# USB_Hub_Switch.net
KiCad netlist of a schematic drawn in EasyEDA Pro
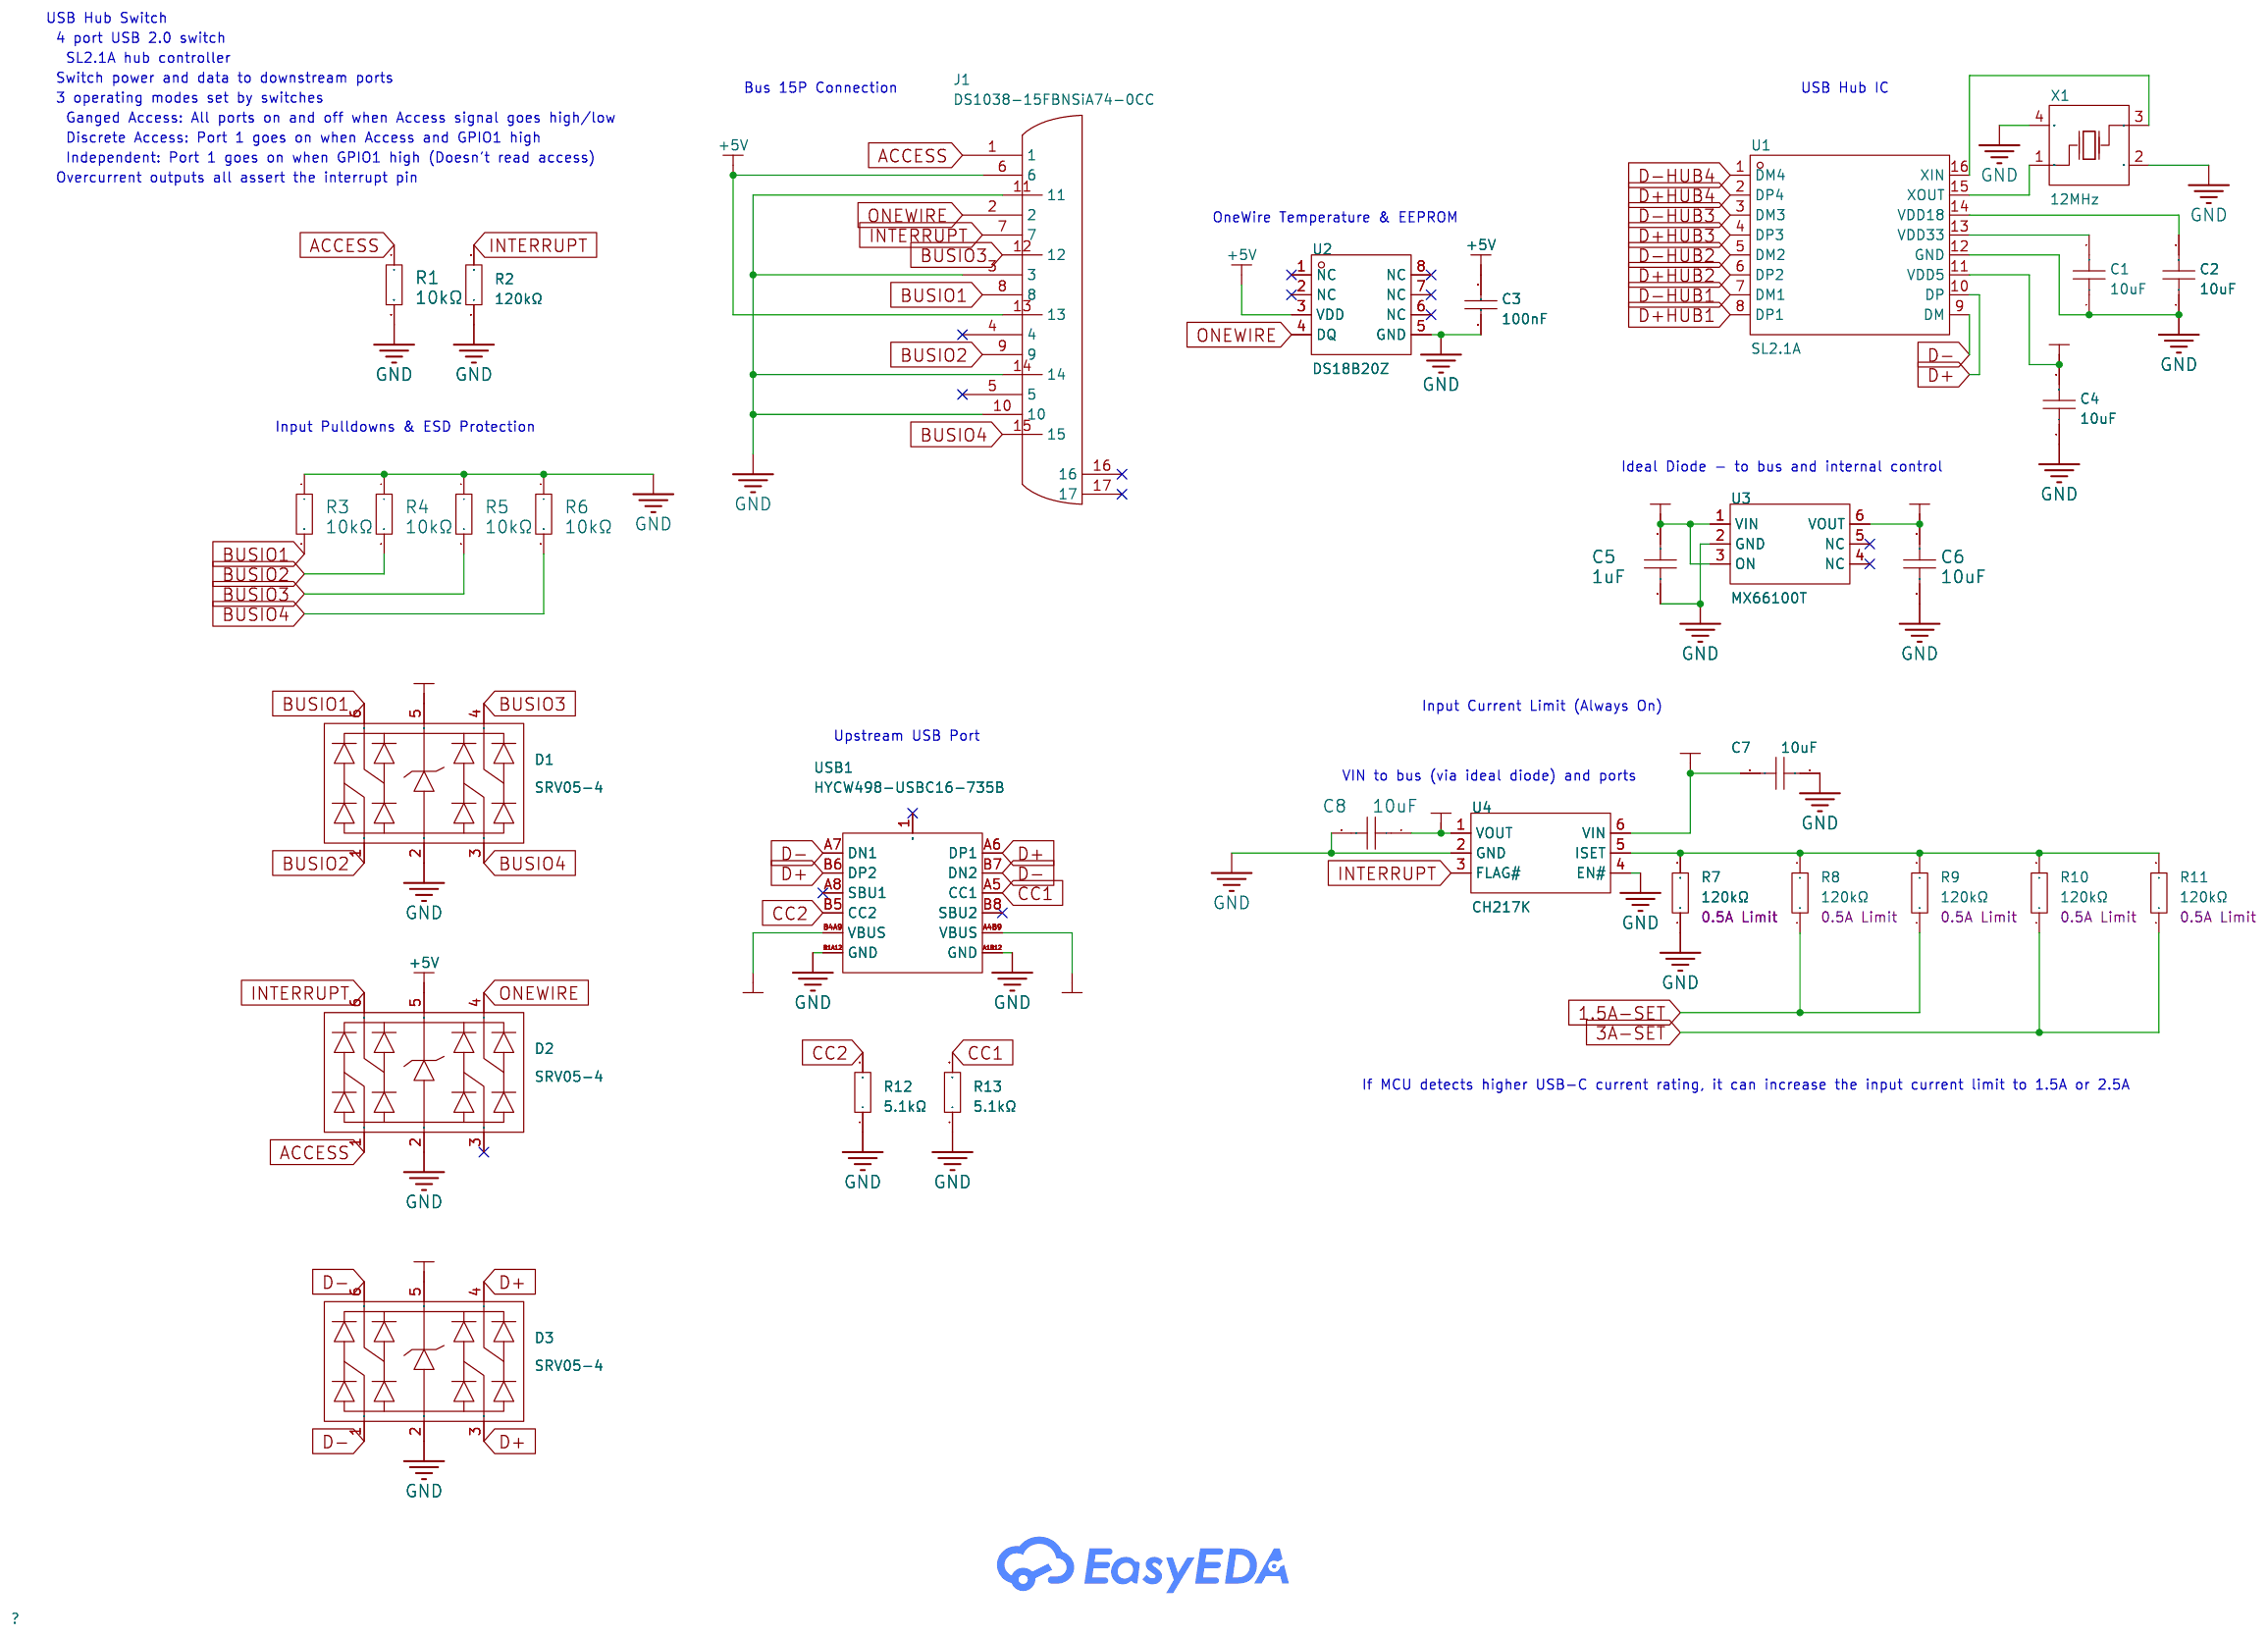
[diagram p0: Upstream Ports]
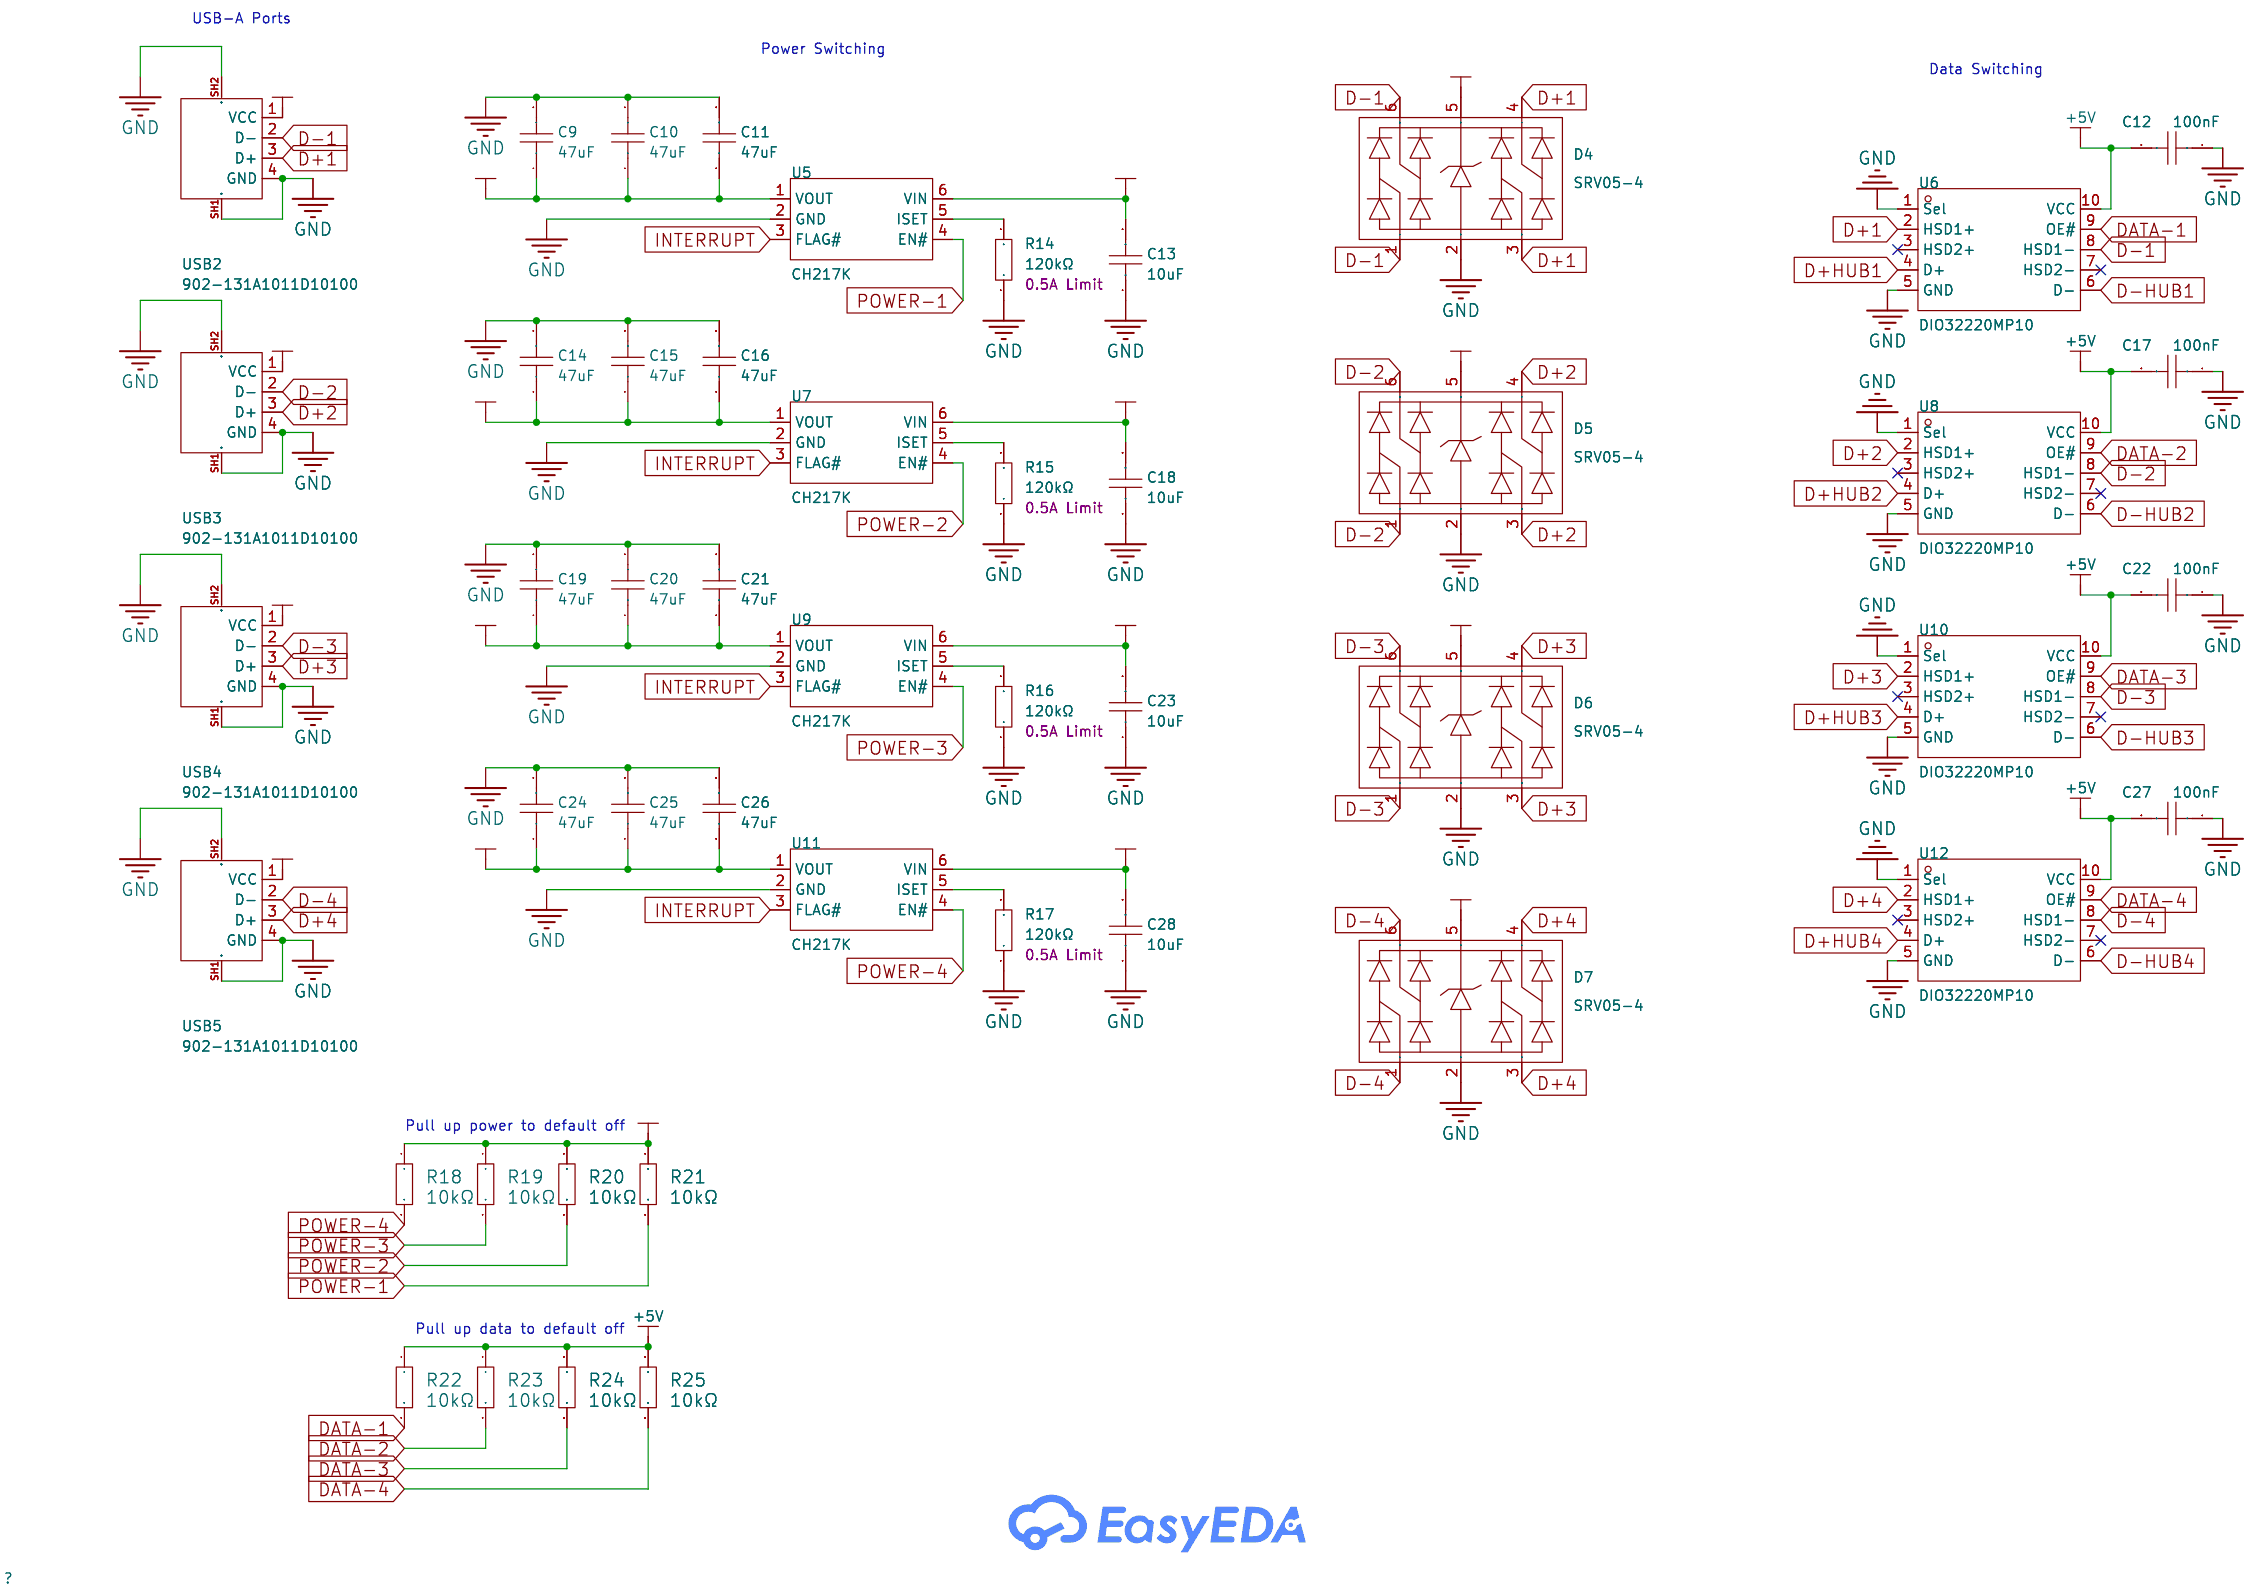
[diagram p1: Downstream Ports]
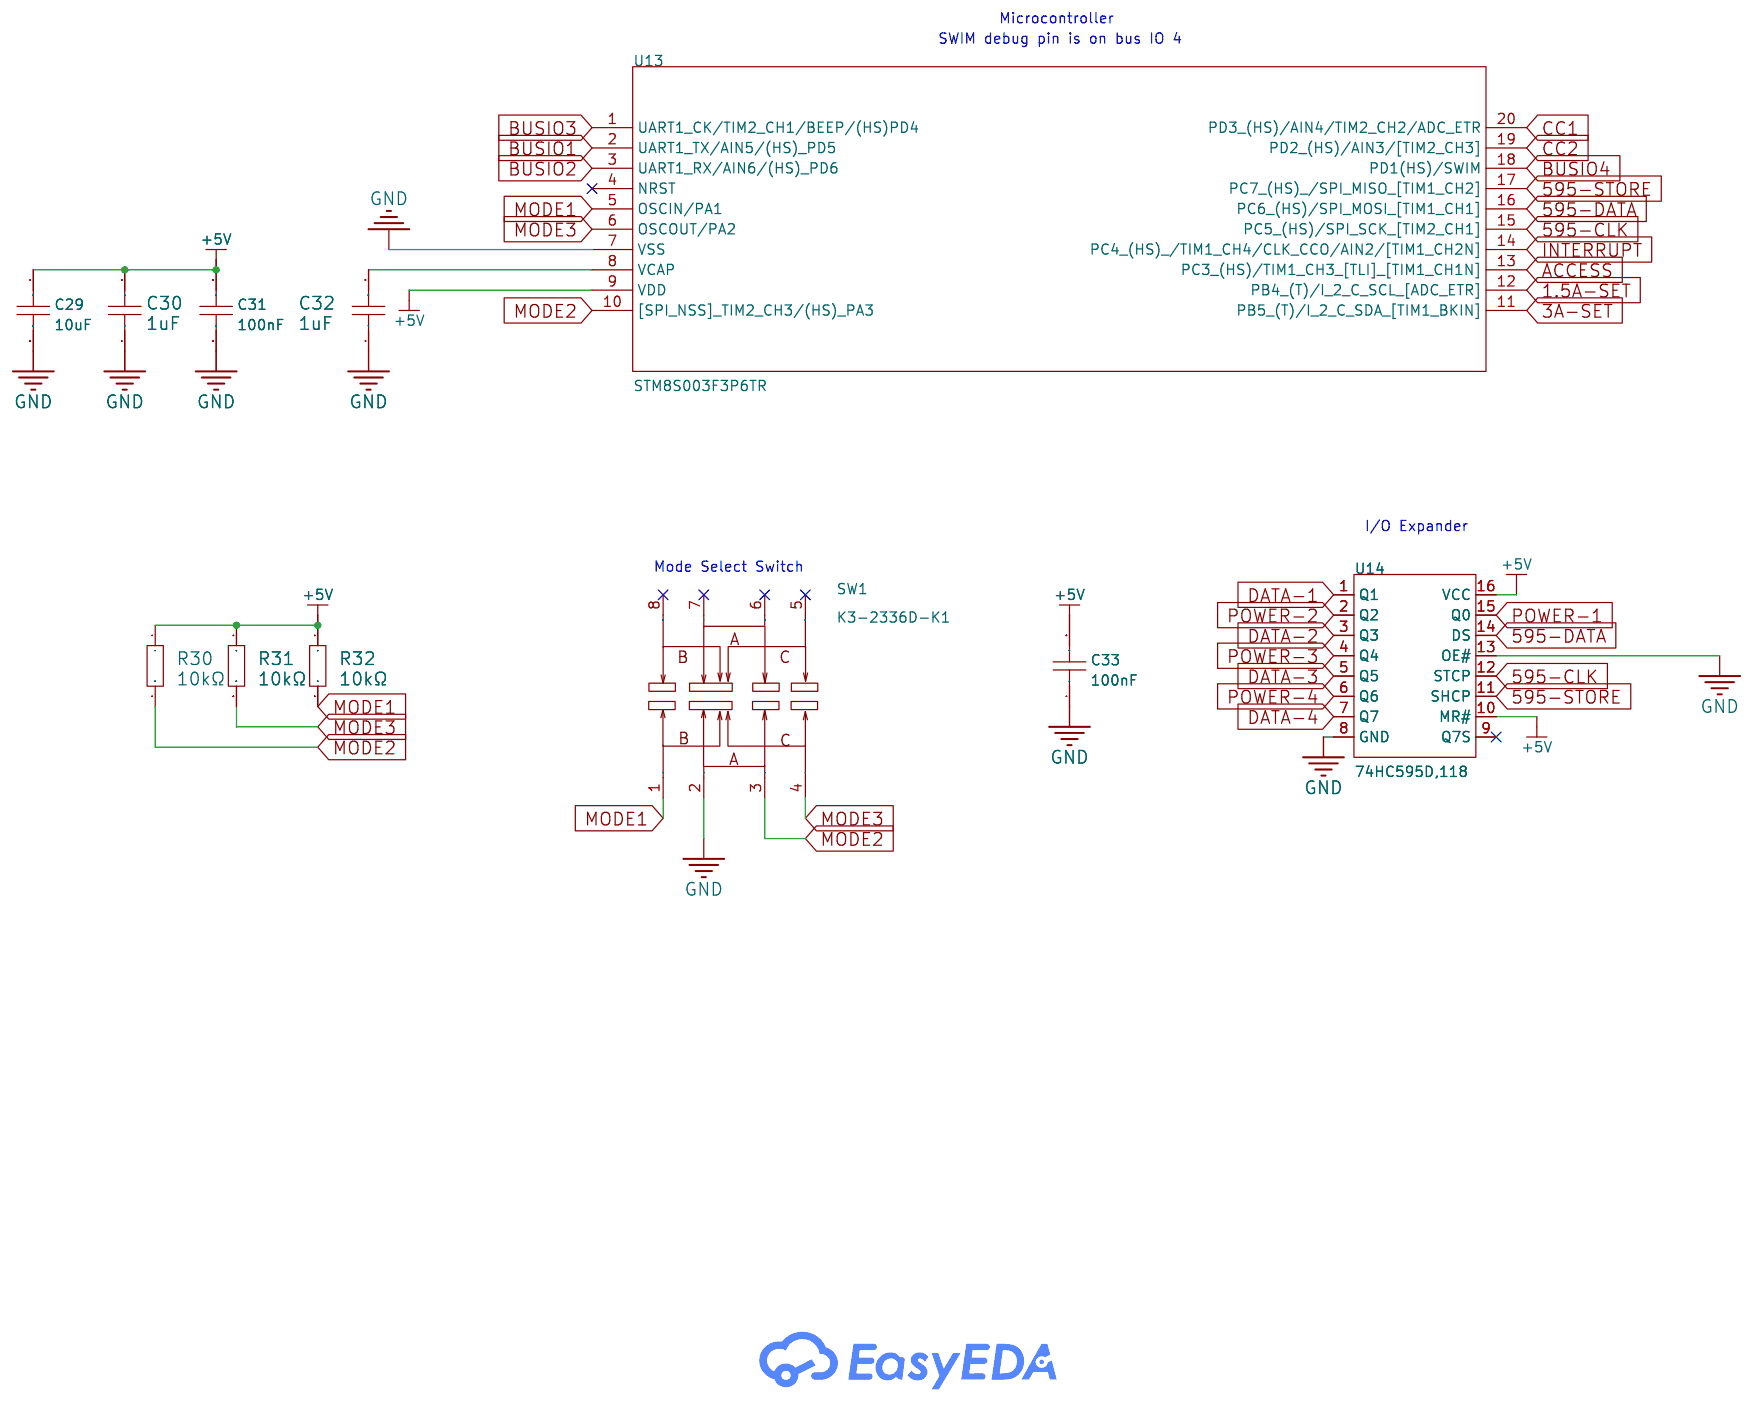
[diagram p2: Microcontroller]
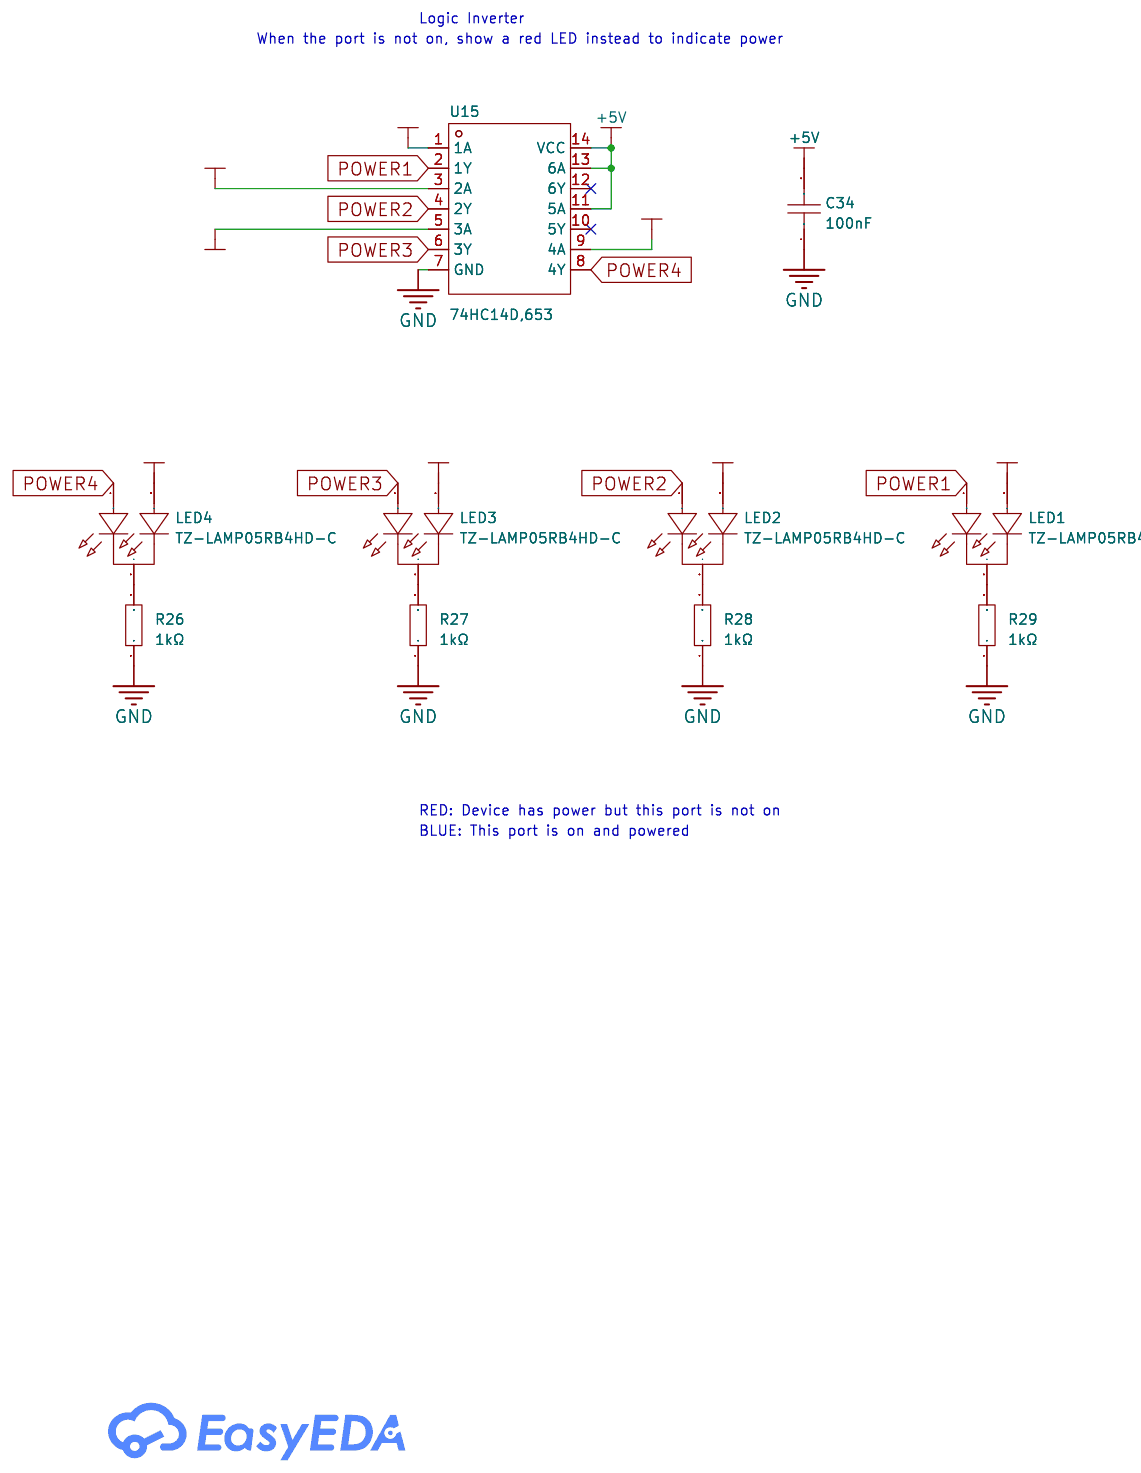
[diagram p3: Status LEDs]

(export (version "E")
  (design (tool "Eeschema 10.0.6"))
  (components
    (comp (ref "C1")
      (value "10uF")
      (footprint "easyedapro:C0603")
      (fields
        (field (name "Manufacturer Part") "CL10A106MA8NRNC")
        (field (name "Manufacturer") "SAMSUNG(三星)")
      )
      (libsource (lib "easyedapro") (part "CL10A106MA8NRNC"))
    )
    (comp (ref "C2")
      (value "10uF")
      (footprint "easyedapro:C0603")
      (fields
        (field (name "Manufacturer Part") "CL10A106MA8NRNC")
        (field (name "Manufacturer") "SAMSUNG(三星)")
      )
      (libsource (lib "easyedapro") (part "CL10A106MA8NRNC"))
    )
    (comp (ref "C3")
      (value "100nF")
      (footprint "easyedapro:C0805")
      (description "Capacitance:100nF Tolerance:±10% Tolerance:±10% Voltage Rating:100V Temperature Coefficient:X7R")
      (fields
        (field (name "Manufacturer Part") "CL21B104KCFNNNE")
        (field (name "Manufacturer") "SAMSUNG(三星)")
      )
      (libsource (lib "easyedapro") (part "CL21B104KCFNNNE"))
    )
    (comp (ref "C4")
      (value "10uF")
      (footprint "easyedapro:C0603")
      (fields
        (field (name "Manufacturer Part") "CL10A106MA8NRNC")
        (field (name "Manufacturer") "SAMSUNG(三星)")
      )
      (libsource (lib "easyedapro") (part "CL10A106MA8NRNC"))
    )
    (comp (ref "C5")
      (value "1uF")
      (footprint "easyedapro:C0603")
      (fields
        (field (name "Manufacturer Part") "CL10A105KB8NNNC")
        (field (name "Manufacturer") "SAMSUNG(三星)")
      )
      (libsource (lib "easyedapro") (part "CL10A105KB8NNNC"))
    )
    (comp (ref "C6")
      (value "10uF")
      (footprint "easyedapro:C0603")
      (description "Capacitance:10uF Tolerance:±20% Tolerance:±20% Voltage Rating:25V Temperature Coefficient:X5R")
      (fields
        (field (name "Manufacturer Part") "CL10A106MA8NRNC")
        (field (name "Manufacturer") "SAMSUNG(三星)")
      )
      (libsource (lib "easyedapro") (part "CL10A106MA8NRNC"))
    )
    (comp (ref "C7")
      (value "10uF")
      (footprint "easyedapro:C0603")
      (fields
        (field (name "Manufacturer Part") "CL10A106MA8NRNC")
        (field (name "Manufacturer") "SAMSUNG(三星)")
      )
      (libsource (lib "easyedapro") (part "CL10A106MA8NRNC"))
    )
    (comp (ref "C8")
      (value "10uF")
      (footprint "easyedapro:C0603")
      (description "Capacitance:10uF Tolerance:±20% Tolerance:±20% Voltage Rating:25V Temperature Coefficient:X5R")
      (fields
        (field (name "Manufacturer Part") "CL10A106MA8NRNC")
        (field (name "Manufacturer") "SAMSUNG(三星)")
      )
      (libsource (lib "easyedapro") (part "CL10A106MA8NRNC"))
    )
    (comp (ref "D1")
      (value "SRV05-4")
      (footprint "easyedapro:SOT-23-6_L2.9-W1.6-P0.95-LS2.8-BL")
      (fields (field (name "Manufacturer") "TECH PUBLIC(台舟)"))
      (libsource (lib "easyedapro") (part "SRV05-4_C558418"))
    )
    (comp (ref "D2")
      (value "SRV05-4")
      (footprint "easyedapro:SOT-23-6_L2.9-W1.6-P0.95-LS2.8-BL")
      (fields (field (name "Manufacturer") "TECH PUBLIC(台舟)"))
      (libsource (lib "easyedapro") (part "SRV05-4_C558418"))
    )
    (comp (ref "D3")
      (value "SRV05-4")
      (footprint "easyedapro:SOT-23-6_L2.9-W1.6-P0.95-LS2.8-BL")
      (fields (field (name "Manufacturer") "TECH PUBLIC(台舟)"))
      (libsource (lib "easyedapro") (part "SRV05-4_C558418"))
    )
    (comp (ref "J1")
      (value "DS1038-15FBNSiA74-0CC")
      (footprint "easyedapro:DSUB-TH_DS1038-15FBNSIA74-0CC")
      (fields (field (name "Manufacturer") "CONNFLY"))
      (libsource (lib "easyedapro") (part "DS1038-15FBNSIA74-0CC"))
    )
    (comp (ref "R1")
      (value "10kΩ")
      (footprint "easyedapro:R0603")
      (fields
        (field (name "Manufacturer Part") "0603WAF1002T5E")
        (field (name "Manufacturer") "UNI-ROYAL(厚声)")
      )
      (libsource (lib "easyedapro") (part "0603WAF1002T5E"))
    )
    (comp (ref "R2")
      (value "120kΩ")
      (footprint "easyedapro:R0603")
      (fields
        (field (name "Manufacturer Part") "0603WAF1203T5E")
        (field (name "Manufacturer") "UNI-ROYAL(厚声)")
      )
      (libsource (lib "easyedapro") (part "0603WAF1203T5E"))
    )
    (comp (ref "R3")
      (value "10kΩ")
      (footprint "easyedapro:R0603")
      (fields
        (field (name "Manufacturer Part") "0603WAF1002T5E")
        (field (name "Manufacturer") "UNI-ROYAL(厚声)")
      )
      (libsource (lib "easyedapro") (part "0603WAF1002T5E"))
    )
    (comp (ref "R4")
      (value "10kΩ")
      (footprint "easyedapro:R0603")
      (fields
        (field (name "Manufacturer Part") "0603WAF1002T5E")
        (field (name "Manufacturer") "UNI-ROYAL(厚声)")
      )
      (libsource (lib "easyedapro") (part "0603WAF1002T5E"))
    )
    (comp (ref "R5")
      (value "10kΩ")
      (footprint "easyedapro:R0603")
      (fields
        (field (name "Manufacturer Part") "0603WAF1002T5E")
        (field (name "Manufacturer") "UNI-ROYAL(厚声)")
      )
      (libsource (lib "easyedapro") (part "0603WAF1002T5E"))
    )
    (comp (ref "R6")
      (value "10kΩ")
      (footprint "easyedapro:R0603")
      (fields
        (field (name "Manufacturer Part") "0603WAF1002T5E")
        (field (name "Manufacturer") "UNI-ROYAL(厚声)")
      )
      (libsource (lib "easyedapro") (part "0603WAF1002T5E"))
    )
    (comp (ref "R7")
      (value "120kΩ")
      (footprint "easyedapro:R0603")
      (fields
        (field (name "Manufacturer Part") "0603WAF1203T5E")
        (field (name "Manufacturer") "UNI-ROYAL(厚声)")
        (field (name "Note") "0.5A Limit")
      )
      (libsource (lib "easyedapro") (part "0603WAF1203T5E"))
    )
    (comp (ref "R8")
      (value "120kΩ")
      (footprint "easyedapro:R0603")
      (fields
        (field (name "Manufacturer Part") "0603WAF1203T5E")
        (field (name "Manufacturer") "UNI-ROYAL(厚声)")
        (field (name "Note") "0.5A Limit")
      )
      (libsource (lib "easyedapro") (part "0603WAF1203T5E"))
    )
    (comp (ref "R9")
      (value "120kΩ")
      (footprint "easyedapro:R0603")
      (fields
        (field (name "Manufacturer Part") "0603WAF1203T5E")
        (field (name "Manufacturer") "UNI-ROYAL(厚声)")
        (field (name "Note") "0.5A Limit")
      )
      (libsource (lib "easyedapro") (part "0603WAF1203T5E"))
    )
    (comp (ref "R10")
      (value "120kΩ")
      (footprint "easyedapro:R0603")
      (fields
        (field (name "Manufacturer Part") "0603WAF1203T5E")
        (field (name "Manufacturer") "UNI-ROYAL(厚声)")
        (field (name "Note") "0.5A Limit")
      )
      (libsource (lib "easyedapro") (part "0603WAF1203T5E"))
    )
    (comp (ref "R11")
      (value "120kΩ")
      (footprint "easyedapro:R0603")
      (fields
        (field (name "Manufacturer Part") "0603WAF1203T5E")
        (field (name "Manufacturer") "UNI-ROYAL(厚声)")
        (field (name "Note") "0.5A Limit")
      )
      (libsource (lib "easyedapro") (part "0603WAF1203T5E"))
    )
    (comp (ref "R12")
      (value "5.1kΩ")
      (footprint "easyedapro:R0603")
      (fields
        (field (name "Manufacturer Part") "0603WAF5101T5E")
        (field (name "Manufacturer") "UNI-ROYAL(厚声)")
      )
      (libsource (lib "easyedapro") (part "0603WAF5101T5E"))
    )
    (comp (ref "R13")
      (value "5.1kΩ")
      (footprint "easyedapro:R0603")
      (fields
        (field (name "Manufacturer Part") "0603WAF5101T5E")
        (field (name "Manufacturer") "UNI-ROYAL(厚声)")
      )
      (libsource (lib "easyedapro") (part "0603WAF5101T5E"))
    )
    (comp (ref "U1")
      (value "SL2.1A")
      (footprint "easyedapro:SOP-16_L10.0-W3.9-P1.27-LS6.0-BL")
      (fields (field (name "Manufacturer") "CoreChips(和芯润德)"))
      (libsource (lib "easyedapro") (part "SL2.1A"))
    )
    (comp (ref "U2")
      (value "DS18B20Z")
      (footprint "easyedapro:SOP-8_L4.9-W3.9-P1.27-LS6.0-BL")
      (description "Resolution:±0.4°C Resolution:±0.4°C Supply Voltage:2.5V~5.5V Supply Voltage:2.5V~5.5V")
      (fields (field (name "Manufacturer") "UMW(友台半导体)"))
      (libsource (lib "easyedapro") (part "DS18B20Z"))
    )
    (comp (ref "U3")
      (value "MX66100T")
      (footprint "easyedapro:SOT-23-6_L2.9-W1.6-P0.95-LS2.9-BL")
      (fields (field (name "Manufacturer") "Wuxi Maxinmicro(无锡明芯微)"))
      (libsource (lib "easyedapro") (part "MX66100T"))
    )
    (comp (ref "U4")
      (value "CH217K")
      (footprint "easyedapro:SOT-23-6_L2.9-W1.6-P0.95-LS2.8-BL")
      (fields (field (name "Manufacturer") "WCH(南京沁恒)"))
      (libsource (lib "easyedapro") (part "CH217K"))
    )
    (comp (ref "USB1")
      (value "HYCW498-USBC16-735B")
      (footprint "easyedapro:USB-C-SMD_HYCW498-USBC16-735B")
      (fields (field (name "Manufacturer") "华宇创"))
      (libsource (lib "easyedapro") (part "HYCW498-USBC16-735B"))
    )
    (comp (ref "X1")
      (value "12MHz")
      (footprint "easyedapro:OSC-SMD_4P-L3.2-W2.5-BL")
      (fields (field (name "Manufacturer Part") "X322512MSB4SI") (field (name "Manufacturer") "YXC(扬兴晶振)"))
      (libsource (lib "easyedapro") (part "X322512MSB4SI"))
    )
    (comp (ref "C9")
      (value "47uF")
      (footprint "easyedapro:C1206")
      (description "Capacitance:47uF Tolerance:±20% Tolerance:±20% Voltage Rating:10V Temperature Coefficient:X5R")
      (fields
        (field (name "Manufacturer Part") "CL31A476MPHNNNE")
        (field (name "Manufacturer") "SAMSUNG(三星)")
      )
      (libsource (lib "easyedapro") (part "CL31A476MPHNNNE"))
    )
    (comp (ref "C10")
      (value "47uF")
      (footprint "easyedapro:C1206")
      (description "Capacitance:47uF Tolerance:±20% Tolerance:±20% Voltage Rating:10V Temperature Coefficient:X5R")
      (fields
        (field (name "Manufacturer Part") "CL31A476MPHNNNE")
        (field (name "Manufacturer") "SAMSUNG(三星)")
      )
      (libsource (lib "easyedapro") (part "CL31A476MPHNNNE"))
    )
    (comp (ref "C11")
      (value "47uF")
      (footprint "easyedapro:C1206")
      (description "Capacitance:47uF Tolerance:±20% Tolerance:±20% Voltage Rating:10V Temperature Coefficient:X5R")
      (fields
        (field (name "Manufacturer Part") "CL31A476MPHNNNE")
        (field (name "Manufacturer") "SAMSUNG(三星)")
      )
      (libsource (lib "easyedapro") (part "CL31A476MPHNNNE"))
    )
    (comp (ref "C12")
      (value "100nF")
      (footprint "easyedapro:C0603")
      (description "Capacitance:100nF Tolerance:±10% Tolerance:±10% Voltage Rating:50V Temperature Coefficient:X7R")
      (fields
        (field (name "Manufacturer Part") "CC0603KRX7R9BB104")
        (field (name "Manufacturer") "YAGEO(国巨)")
      )
      (libsource (lib "easyedapro") (part "CC0603KRX7R9BB104"))
    )
    (comp (ref "C13")
      (value "10uF")
      (footprint "easyedapro:C0603")
      (fields
        (field (name "Manufacturer Part") "CL10A106MA8NRNC")
        (field (name "Manufacturer") "SAMSUNG(三星)")
      )
      (libsource (lib "easyedapro") (part "CL10A106MA8NRNC"))
    )
    (comp (ref "C14")
      (value "47uF")
      (footprint "easyedapro:C1206")
      (description "Capacitance:47uF Tolerance:±20% Tolerance:±20% Voltage Rating:10V Temperature Coefficient:X5R")
      (fields
        (field (name "Manufacturer Part") "CL31A476MPHNNNE")
        (field (name "Manufacturer") "SAMSUNG(三星)")
      )
      (libsource (lib "easyedapro") (part "CL31A476MPHNNNE"))
    )
    (comp (ref "C15")
      (value "47uF")
      (footprint "easyedapro:C1206")
      (description "Capacitance:47uF Tolerance:±20% Tolerance:±20% Voltage Rating:10V Temperature Coefficient:X5R")
      (fields
        (field (name "Manufacturer Part") "CL31A476MPHNNNE")
        (field (name "Manufacturer") "SAMSUNG(三星)")
      )
      (libsource (lib "easyedapro") (part "CL31A476MPHNNNE"))
    )
    (comp (ref "C16")
      (value "47uF")
      (footprint "easyedapro:C1206")
      (description "Capacitance:47uF Tolerance:±20% Tolerance:±20% Voltage Rating:10V Temperature Coefficient:X5R")
      (fields
        (field (name "Manufacturer Part") "CL31A476MPHNNNE")
        (field (name "Manufacturer") "SAMSUNG(三星)")
      )
      (libsource (lib "easyedapro") (part "CL31A476MPHNNNE"))
    )
    (comp (ref "C17")
      (value "100nF")
      (footprint "easyedapro:C0603")
      (description "Capacitance:100nF Tolerance:±10% Tolerance:±10% Voltage Rating:50V Temperature Coefficient:X7R")
      (fields
        (field (name "Manufacturer Part") "CC0603KRX7R9BB104")
        (field (name "Manufacturer") "YAGEO(国巨)")
      )
      (libsource (lib "easyedapro") (part "CC0603KRX7R9BB104"))
    )
    (comp (ref "C18")
      (value "10uF")
      (footprint "easyedapro:C0603")
      (fields
        (field (name "Manufacturer Part") "CL10A106MA8NRNC")
        (field (name "Manufacturer") "SAMSUNG(三星)")
      )
      (libsource (lib "easyedapro") (part "CL10A106MA8NRNC"))
    )
    (comp (ref "C19")
      (value "47uF")
      (footprint "easyedapro:C1206")
      (description "Capacitance:47uF Tolerance:±20% Tolerance:±20% Voltage Rating:10V Temperature Coefficient:X5R")
      (fields
        (field (name "Manufacturer Part") "CL31A476MPHNNNE")
        (field (name "Manufacturer") "SAMSUNG(三星)")
      )
      (libsource (lib "easyedapro") (part "CL31A476MPHNNNE"))
    )
    (comp (ref "C20")
      (value "47uF")
      (footprint "easyedapro:C1206")
      (description "Capacitance:47uF Tolerance:±20% Tolerance:±20% Voltage Rating:10V Temperature Coefficient:X5R")
      (fields
        (field (name "Manufacturer Part") "CL31A476MPHNNNE")
        (field (name "Manufacturer") "SAMSUNG(三星)")
      )
      (libsource (lib "easyedapro") (part "CL31A476MPHNNNE"))
    )
    (comp (ref "C21")
      (value "47uF")
      (footprint "easyedapro:C1206")
      (description "Capacitance:47uF Tolerance:±20% Tolerance:±20% Voltage Rating:10V Temperature Coefficient:X5R")
      (fields
        (field (name "Manufacturer Part") "CL31A476MPHNNNE")
        (field (name "Manufacturer") "SAMSUNG(三星)")
      )
      (libsource (lib "easyedapro") (part "CL31A476MPHNNNE"))
    )
    (comp (ref "C22")
      (value "100nF")
      (footprint "easyedapro:C0603")
      (description "Capacitance:100nF Tolerance:±10% Tolerance:±10% Voltage Rating:50V Temperature Coefficient:X7R")
      (fields
        (field (name "Manufacturer Part") "CC0603KRX7R9BB104")
        (field (name "Manufacturer") "YAGEO(国巨)")
      )
      (libsource (lib "easyedapro") (part "CC0603KRX7R9BB104"))
    )
    (comp (ref "C23")
      (value "10uF")
      (footprint "easyedapro:C0603")
      (fields
        (field (name "Manufacturer Part") "CL10A106MA8NRNC")
        (field (name "Manufacturer") "SAMSUNG(三星)")
      )
      (libsource (lib "easyedapro") (part "CL10A106MA8NRNC"))
    )
    (comp (ref "C24")
      (value "47uF")
      (footprint "easyedapro:C1206")
      (description "Capacitance:47uF Tolerance:±20% Tolerance:±20% Voltage Rating:10V Temperature Coefficient:X5R")
      (fields
        (field (name "Manufacturer Part") "CL31A476MPHNNNE")
        (field (name "Manufacturer") "SAMSUNG(三星)")
      )
      (libsource (lib "easyedapro") (part "CL31A476MPHNNNE"))
    )
    (comp (ref "C25")
      (value "47uF")
      (footprint "easyedapro:C1206")
      (description "Capacitance:47uF Tolerance:±20% Tolerance:±20% Voltage Rating:10V Temperature Coefficient:X5R")
      (fields
        (field (name "Manufacturer Part") "CL31A476MPHNNNE")
        (field (name "Manufacturer") "SAMSUNG(三星)")
      )
      (libsource (lib "easyedapro") (part "CL31A476MPHNNNE"))
    )
    (comp (ref "C26")
      (value "47uF")
      (footprint "easyedapro:C1206")
      (description "Capacitance:47uF Tolerance:±20% Tolerance:±20% Voltage Rating:10V Temperature Coefficient:X5R")
      (fields
        (field (name "Manufacturer Part") "CL31A476MPHNNNE")
        (field (name "Manufacturer") "SAMSUNG(三星)")
      )
      (libsource (lib "easyedapro") (part "CL31A476MPHNNNE"))
    )
    (comp (ref "C27")
      (value "100nF")
      (footprint "easyedapro:C0603")
      (description "Capacitance:100nF Tolerance:±10% Tolerance:±10% Voltage Rating:50V Temperature Coefficient:X7R")
      (fields
        (field (name "Manufacturer Part") "CC0603KRX7R9BB104")
        (field (name "Manufacturer") "YAGEO(国巨)")
      )
      (libsource (lib "easyedapro") (part "CC0603KRX7R9BB104"))
    )
    (comp (ref "C28")
      (value "10uF")
      (footprint "easyedapro:C0603")
      (fields
        (field (name "Manufacturer Part") "CL10A106MA8NRNC")
        (field (name "Manufacturer") "SAMSUNG(三星)")
      )
      (libsource (lib "easyedapro") (part "CL10A106MA8NRNC"))
    )
    (comp (ref "D4")
      (value "SRV05-4")
      (footprint "easyedapro:SOT-23-6_L2.9-W1.6-P0.95-LS2.8-BL")
      (fields (field (name "Manufacturer") "TECH PUBLIC(台舟)"))
      (libsource (lib "easyedapro") (part "SRV05-4_C558418"))
    )
    (comp (ref "D5")
      (value "SRV05-4")
      (footprint "easyedapro:SOT-23-6_L2.9-W1.6-P0.95-LS2.8-BL")
      (fields (field (name "Manufacturer") "TECH PUBLIC(台舟)"))
      (libsource (lib "easyedapro") (part "SRV05-4_C558418"))
    )
    (comp (ref "D6")
      (value "SRV05-4")
      (footprint "easyedapro:SOT-23-6_L2.9-W1.6-P0.95-LS2.8-BL")
      (fields (field (name "Manufacturer") "TECH PUBLIC(台舟)"))
      (libsource (lib "easyedapro") (part "SRV05-4_C558418"))
    )
    (comp (ref "D7")
      (value "SRV05-4")
      (footprint "easyedapro:SOT-23-6_L2.9-W1.6-P0.95-LS2.8-BL")
      (fields (field (name "Manufacturer") "TECH PUBLIC(台舟)"))
      (libsource (lib "easyedapro") (part "SRV05-4_C558418"))
    )
    (comp (ref "R14")
      (value "120kΩ")
      (footprint "easyedapro:R0603")
      (fields
        (field (name "Manufacturer Part") "0603WAF1203T5E")
        (field (name "Manufacturer") "UNI-ROYAL(厚声)")
        (field (name "Note") "0.5A Limit")
      )
      (libsource (lib "easyedapro") (part "0603WAF1203T5E"))
    )
    (comp (ref "R15")
      (value "120kΩ")
      (footprint "easyedapro:R0603")
      (fields
        (field (name "Manufacturer Part") "0603WAF1203T5E")
        (field (name "Manufacturer") "UNI-ROYAL(厚声)")
        (field (name "Note") "0.5A Limit")
      )
      (libsource (lib "easyedapro") (part "0603WAF1203T5E"))
    )
    (comp (ref "R16")
      (value "120kΩ")
      (footprint "easyedapro:R0603")
      (fields
        (field (name "Manufacturer Part") "0603WAF1203T5E")
        (field (name "Manufacturer") "UNI-ROYAL(厚声)")
        (field (name "Note") "0.5A Limit")
      )
      (libsource (lib "easyedapro") (part "0603WAF1203T5E"))
    )
    (comp (ref "R17")
      (value "120kΩ")
      (footprint "easyedapro:R0603")
      (fields
        (field (name "Manufacturer Part") "0603WAF1203T5E")
        (field (name "Manufacturer") "UNI-ROYAL(厚声)")
        (field (name "Note") "0.5A Limit")
      )
      (libsource (lib "easyedapro") (part "0603WAF1203T5E"))
    )
    (comp (ref "R18")
      (value "10kΩ")
      (footprint "easyedapro:R0603")
      (fields
        (field (name "Manufacturer Part") "0603WAF1002T5E")
        (field (name "Manufacturer") "UNI-ROYAL(厚声)")
      )
      (libsource (lib "easyedapro") (part "0603WAF1002T5E"))
    )
    (comp (ref "R19")
      (value "10kΩ")
      (footprint "easyedapro:R0603")
      (fields
        (field (name "Manufacturer Part") "0603WAF1002T5E")
        (field (name "Manufacturer") "UNI-ROYAL(厚声)")
      )
      (libsource (lib "easyedapro") (part "0603WAF1002T5E"))
    )
    (comp (ref "R20")
      (value "10kΩ")
      (footprint "easyedapro:R0603")
      (fields
        (field (name "Manufacturer Part") "0603WAF1002T5E")
        (field (name "Manufacturer") "UNI-ROYAL(厚声)")
      )
      (libsource (lib "easyedapro") (part "0603WAF1002T5E"))
    )
    (comp (ref "R21")
      (value "10kΩ")
      (footprint "easyedapro:R0603")
      (fields
        (field (name "Manufacturer Part") "0603WAF1002T5E")
        (field (name "Manufacturer") "UNI-ROYAL(厚声)")
      )
      (libsource (lib "easyedapro") (part "0603WAF1002T5E"))
    )
    (comp (ref "R22")
      (value "10kΩ")
      (footprint "easyedapro:R0603")
      (fields
        (field (name "Manufacturer Part") "0603WAF1002T5E")
        (field (name "Manufacturer") "UNI-ROYAL(厚声)")
      )
      (libsource (lib "easyedapro") (part "0603WAF1002T5E"))
    )
    (comp (ref "R23")
      (value "10kΩ")
      (footprint "easyedapro:R0603")
      (fields
        (field (name "Manufacturer Part") "0603WAF1002T5E")
        (field (name "Manufacturer") "UNI-ROYAL(厚声)")
      )
      (libsource (lib "easyedapro") (part "0603WAF1002T5E"))
    )
    (comp (ref "R24")
      (value "10kΩ")
      (footprint "easyedapro:R0603")
      (fields
        (field (name "Manufacturer Part") "0603WAF1002T5E")
        (field (name "Manufacturer") "UNI-ROYAL(厚声)")
      )
      (libsource (lib "easyedapro") (part "0603WAF1002T5E"))
    )
    (comp (ref "R25")
      (value "10kΩ")
      (footprint "easyedapro:R0603")
      (fields
        (field (name "Manufacturer Part") "0603WAF1002T5E")
        (field (name "Manufacturer") "UNI-ROYAL(厚声)")
      )
      (libsource (lib "easyedapro") (part "0603WAF1002T5E"))
    )
    (comp (ref "U5")
      (value "CH217K")
      (footprint "easyedapro:SOT-23-6_L2.9-W1.6-P0.95-LS2.8-BL")
      (fields (field (name "Manufacturer") "WCH(南京沁恒)"))
      (libsource (lib "easyedapro") (part "CH217K"))
    )
    (comp (ref "U6")
      (value "DIO32220MP10")
      (footprint "easyedapro:MSOP-10_L3.0-W3.0-P0.50-LS5.0-BL")
      (fields (field (name "Manufacturer") "DIOO(帝奥微)"))
      (libsource (lib "easyedapro") (part "DIO32220MP10"))
    )
    (comp (ref "U7")
      (value "CH217K")
      (footprint "easyedapro:SOT-23-6_L2.9-W1.6-P0.95-LS2.8-BL")
      (fields (field (name "Manufacturer") "WCH(南京沁恒)"))
      (libsource (lib "easyedapro") (part "CH217K"))
    )
    (comp (ref "U8")
      (value "DIO32220MP10")
      (footprint "easyedapro:MSOP-10_L3.0-W3.0-P0.50-LS5.0-BL")
      (fields (field (name "Manufacturer") "DIOO(帝奥微)"))
      (libsource (lib "easyedapro") (part "DIO32220MP10"))
    )
    (comp (ref "U9")
      (value "CH217K")
      (footprint "easyedapro:SOT-23-6_L2.9-W1.6-P0.95-LS2.8-BL")
      (fields (field (name "Manufacturer") "WCH(南京沁恒)"))
      (libsource (lib "easyedapro") (part "CH217K"))
    )
    (comp (ref "U10")
      (value "DIO32220MP10")
      (footprint "easyedapro:MSOP-10_L3.0-W3.0-P0.50-LS5.0-BL")
      (fields (field (name "Manufacturer") "DIOO(帝奥微)"))
      (libsource (lib "easyedapro") (part "DIO32220MP10"))
    )
    (comp (ref "U11")
      (value "CH217K")
      (footprint "easyedapro:SOT-23-6_L2.9-W1.6-P0.95-LS2.8-BL")
      (fields (field (name "Manufacturer") "WCH(南京沁恒)"))
      (libsource (lib "easyedapro") (part "CH217K"))
    )
    (comp (ref "U12")
      (value "DIO32220MP10")
      (footprint "easyedapro:MSOP-10_L3.0-W3.0-P0.50-LS5.0-BL")
      (fields (field (name "Manufacturer") "DIOO(帝奥微)"))
      (libsource (lib "easyedapro") (part "DIO32220MP10"))
    )
    (comp (ref "USB2")
      (value "902-131A1011D10100")
      (footprint "easyedapro:USB-A-TH__USB-AF-90")
      (fields (field (name "Manufacturer") "精拓金"))
      (libsource (lib "easyedapro") (part "JTJ-USB-AF-08"))
    )
    (comp (ref "USB3")
      (value "902-131A1011D10100")
      (footprint "easyedapro:USB-A-TH__USB-AF-90")
      (fields (field (name "Manufacturer") "精拓金"))
      (libsource (lib "easyedapro") (part "JTJ-USB-AF-08"))
    )
    (comp (ref "USB4")
      (value "902-131A1011D10100")
      (footprint "easyedapro:USB-A-TH__USB-AF-90")
      (fields (field (name "Manufacturer") "精拓金"))
      (libsource (lib "easyedapro") (part "JTJ-USB-AF-08"))
    )
    (comp (ref "USB5")
      (value "902-131A1011D10100")
      (footprint "easyedapro:USB-A-TH__USB-AF-90")
      (fields (field (name "Manufacturer") "精拓金"))
      (libsource (lib "easyedapro") (part "JTJ-USB-AF-08"))
    )
    (comp (ref "C29")
      (value "10uF")
      (footprint "easyedapro:C0603")
      (fields
        (field (name "Manufacturer Part") "CL10A106MA8NRNC")
        (field (name "Manufacturer") "SAMSUNG(三星)")
      )
      (libsource (lib "easyedapro") (part "CL10A106MA8NRNC"))
    )
    (comp (ref "C30")
      (value "1uF")
      (footprint "easyedapro:C0603")
      (fields
        (field (name "Manufacturer Part") "CL10A105KB8NNNC")
        (field (name "Manufacturer") "SAMSUNG(三星)")
      )
      (libsource (lib "easyedapro") (part "CL10A105KB8NNNC"))
    )
    (comp (ref "C31")
      (value "100nF")
      (footprint "easyedapro:C0603")
      (description "Capacitance:100nF Tolerance:±10% Tolerance:±10% Voltage Rating:50V Temperature Coefficient:X7R")
      (fields
        (field (name "Manufacturer Part") "CC0603KRX7R9BB104")
        (field (name "Manufacturer") "YAGEO(国巨)")
      )
      (libsource (lib "easyedapro") (part "CC0603KRX7R9BB104"))
    )
    (comp (ref "C32")
      (value "1uF")
      (footprint "easyedapro:C0603")
      (fields
        (field (name "Manufacturer Part") "CL10A105KB8NNNC")
        (field (name "Manufacturer") "SAMSUNG(三星)")
      )
      (libsource (lib "easyedapro") (part "CL10A105KB8NNNC"))
    )
    (comp (ref "C33")
      (value "100nF")
      (footprint "easyedapro:C0603")
      (description "Capacitance:100nF Tolerance:±10% Tolerance:±10% Voltage Rating:50V Temperature Coefficient:X7R")
      (fields
        (field (name "Manufacturer Part") "CC0603KRX7R9BB104")
        (field (name "Manufacturer") "YAGEO(国巨)")
      )
      (libsource (lib "easyedapro") (part "CC0603KRX7R9BB104"))
    )
    (comp (ref "R30")
      (value "10kΩ")
      (footprint "easyedapro:R0603")
      (fields
        (field (name "Manufacturer Part") "0603WAF1002T5E")
        (field (name "Manufacturer") "UNI-ROYAL(厚声)")
      )
      (libsource (lib "easyedapro") (part "0603WAF1002T5E"))
    )
    (comp (ref "R31")
      (value "10kΩ")
      (footprint "easyedapro:R0603")
      (fields
        (field (name "Manufacturer Part") "0603WAF1002T5E")
        (field (name "Manufacturer") "UNI-ROYAL(厚声)")
      )
      (libsource (lib "easyedapro") (part "0603WAF1002T5E"))
    )
    (comp (ref "R32")
      (value "10kΩ")
      (footprint "easyedapro:R0603")
      (fields
        (field (name "Manufacturer Part") "0603WAF1002T5E")
        (field (name "Manufacturer") "UNI-ROYAL(厚声)")
      )
      (libsource (lib "easyedapro") (part "0603WAF1002T5E"))
    )
    (comp (ref "SW1")
      (value "K3-2336D-K1")
      (footprint "easyedapro:SW-TH_K3-2336D-K1")
      (fields (field (name "Manufacturer") "韩国韩荣"))
      (libsource (lib "easyedapro") (part "K3-2336D-K1"))
    )
    (comp (ref "U13")
      (value "STM8S003F3P6TR")
      (footprint "easyedapro:TSSOP-20_L6.5-W4.4-P0.65-LS6.4-BL")
      (fields (field (name "Manufacturer") "ST(意法半导体)"))
      (libsource (lib "easyedapro") (part "STM8S003F3P6TR"))
    )
    (comp (ref "U14")
      (value "74HC595D,118")
      (footprint "easyedapro:SOIC-16_L9.9-W3.9-P1.27-LS6.0-BL")
      (fields (field (name "Manufacturer") "Nexperia(安世)"))
      (libsource (lib "easyedapro") (part "74HC595D,118"))
    )
    (comp (ref "C34")
      (value "100nF")
      (footprint "easyedapro:C0603")
      (description "Capacitance:100nF Tolerance:±10% Tolerance:±10% Voltage Rating:50V Temperature Coefficient:X7R")
      (fields
        (field (name "Manufacturer Part") "CC0603KRX7R9BB104")
        (field (name "Manufacturer") "YAGEO(国巨)")
      )
      (libsource (lib "easyedapro") (part "CC0603KRX7R9BB104"))
    )
    (comp (ref "LED1")
      (value "TZ-LAMP05RB4HD-C")
      (footprint "easyedapro:LED-TH_3P-BD5.8-P2.54-R-BI")
      (fields (field (name "Manufacturer") "TUOZHAN(拓展光电)"))
      (libsource (lib "easyedapro") (part "TZ-LAMP05RB4HD-C"))
    )
    (comp (ref "LED2")
      (value "TZ-LAMP05RB4HD-C")
      (footprint "easyedapro:LED-TH_3P-BD5.8-P2.54-R-BI")
      (fields (field (name "Manufacturer") "TUOZHAN(拓展光电)"))
      (libsource (lib "easyedapro") (part "TZ-LAMP05RB4HD-C"))
    )
    (comp (ref "LED3")
      (value "TZ-LAMP05RB4HD-C")
      (footprint "easyedapro:LED-TH_3P-BD5.8-P2.54-R-BI")
      (fields (field (name "Manufacturer") "TUOZHAN(拓展光电)"))
      (libsource (lib "easyedapro") (part "TZ-LAMP05RB4HD-C"))
    )
    (comp (ref "LED4")
      (value "TZ-LAMP05RB4HD-C")
      (footprint "easyedapro:LED-TH_3P-BD5.8-P2.54-R-BI")
      (fields (field (name "Manufacturer") "TUOZHAN(拓展光电)"))
      (libsource (lib "easyedapro") (part "TZ-LAMP05RB4HD-C"))
    )
    (comp (ref "R26")
      (value "1kΩ")
      (footprint "easyedapro:R0805")
      (fields
        (field (name "Manufacturer Part") "0805W8F1001T5E")
        (field (name "Manufacturer") "UNI-ROYAL(厚声)")
      )
      (libsource (lib "easyedapro") (part "0805W8F1001T5E"))
    )
    (comp (ref "R27")
      (value "1kΩ")
      (footprint "easyedapro:R0805")
      (fields
        (field (name "Manufacturer Part") "0805W8F1001T5E")
        (field (name "Manufacturer") "UNI-ROYAL(厚声)")
      )
      (libsource (lib "easyedapro") (part "0805W8F1001T5E"))
    )
    (comp (ref "R28")
      (value "1kΩ")
      (footprint "easyedapro:R0805")
      (fields
        (field (name "Manufacturer Part") "0805W8F1001T5E")
        (field (name "Manufacturer") "UNI-ROYAL(厚声)")
      )
      (libsource (lib "easyedapro") (part "0805W8F1001T5E"))
    )
    (comp (ref "R29")
      (value "1kΩ")
      (footprint "easyedapro:R0805")
      (fields
        (field (name "Manufacturer Part") "0805W8F1001T5E")
        (field (name "Manufacturer") "UNI-ROYAL(厚声)")
      )
      (libsource (lib "easyedapro") (part "0805W8F1001T5E"))
    )
    (comp (ref "U15")
      (value "74HC14D,653")
      (footprint "easyedapro:SOIC-14_L8.7-W3.9-P1.27-LS6.0-BL")
      (fields (field (name "Manufacturer") "Nexperia(安世)"))
      (libsource (lib "easyedapro") (part "74HC14D,653"))
    )
  )
  (nets
    (net (code "1") (name "+5V") (class "Default")
      (node (ref "C12") (pin "2") (pinfunction "2_2") (pintype "unspecified"))
      (node (ref "C17") (pin "2") (pinfunction "2_2") (pintype "unspecified"))
      (node (ref "C22") (pin "2") (pinfunction "2_2") (pintype "unspecified"))
      (node (ref "C27") (pin "2") (pinfunction "2_2") (pintype "unspecified"))
      (node (ref "C29") (pin "1") (pinfunction "1_1") (pintype "input"))
      (node (ref "C3") (pin "2") (pinfunction "2_2") (pintype "input"))
      (node (ref "C30") (pin "2") (pinfunction "2_2") (pintype "unspecified"))
      (node (ref "C31") (pin "2") (pinfunction "2_2") (pintype "unspecified"))
      (node (ref "C33") (pin "2") (pinfunction "2_2") (pintype "unspecified"))
      (node (ref "C34") (pin "2") (pinfunction "2_2") (pintype "unspecified"))
      (node (ref "C6") (pin "2") (pinfunction "2_2") (pintype "input"))
      (node (ref "D1") (pin "5") (pinfunction "5_5") (pintype "unspecified"))
      (node (ref "D2") (pin "5") (pinfunction "5_5") (pintype "unspecified"))
      (node (ref "J1") (pin "13") (pinfunction "13_13") (pintype "unspecified"))
      (node (ref "J1") (pin "6") (pinfunction "6_6") (pintype "unspecified"))
      (node (ref "R22") (pin "1") (pinfunction "1_1") (pintype "input"))
      (node (ref "R23") (pin "1") (pinfunction "1_1") (pintype "input"))
      (node (ref "R24") (pin "1") (pinfunction "1_1") (pintype "input"))
      (node (ref "R25") (pin "1") (pinfunction "1_1") (pintype "input"))
      (node (ref "R30") (pin "1") (pinfunction "1_1") (pintype "input"))
      (node (ref "R31") (pin "1") (pinfunction "1_1") (pintype "input"))
      (node (ref "R32") (pin "1") (pinfunction "1_1") (pintype "input"))
      (node (ref "U10") (pin "10") (pinfunction "VCC_10") (pintype "unspecified"))
      (node (ref "U12") (pin "10") (pinfunction "VCC_10") (pintype "unspecified"))
      (node (ref "U13") (pin "9") (pinfunction "VDD_9") (pintype "unspecified"))
      (node (ref "U14") (pin "10") (pinfunction "MR#_10") (pintype "unspecified"))
      (node (ref "U14") (pin "16") (pinfunction "VCC_16") (pintype "unspecified"))
      (node (ref "U15") (pin "11") (pinfunction "5A_11") (pintype "unspecified"))
      (node (ref "U15") (pin "13") (pinfunction "6A_13") (pintype "unspecified"))
      (node (ref "U15") (pin "14") (pinfunction "VCC_14") (pintype "unspecified"))
      (node (ref "U2") (pin "3") (pinfunction "VDD_3") (pintype "unspecified"))
      (node (ref "U3") (pin "6") (pinfunction "VOUT_6") (pintype "unspecified"))
      (node (ref "U6") (pin "10") (pinfunction "VCC_10") (pintype "unspecified"))
      (node (ref "U8") (pin "10") (pinfunction "VCC_10") (pintype "unspecified"))
    )
    (net (code "2") (name "1.5A-SET") (class "Default")
      (node (ref "R8") (pin "1") (pinfunction "1_1") (pintype "input"))
      (node (ref "R9") (pin "1") (pinfunction "1_1") (pintype "input"))
      (node (ref "U13") (pin "12") (pinfunction "PB4_(T)/I_2_C_SCL_[ADC_ETR]_12") (pintype "unspecified"))
    )
    (net (code "3") (name "3A-SET") (class "Default")
      (node (ref "R10") (pin "1") (pinfunction "1_1") (pintype "input"))
      (node (ref "R11") (pin "1") (pinfunction "1_1") (pintype "input"))
      (node (ref "U13") (pin "11") (pinfunction "PB5_(T)/I_2_C_SDA_[TIM1_BKIN]_11") (pintype "unspecified"))
    )
    (net (code "4") (name "595-CLK") (class "Default")
      (node (ref "U13") (pin "15") (pinfunction "PC5_(HS)/SPI_SCK_[TIM2_CH1]_15") (pintype "unspecified"))
      (node (ref "U14") (pin "12") (pinfunction "STCP_12") (pintype "unspecified"))
    )
    (net (code "5") (name "595-DATA") (class "Default")
      (node (ref "U13") (pin "16") (pinfunction "PC6_(HS)/SPI_MOSI_[TIM1_CH1]_16") (pintype "unspecified"))
      (node (ref "U14") (pin "14") (pinfunction "DS_14") (pintype "unspecified"))
    )
    (net (code "6") (name "595-STORE") (class "Default")
      (node (ref "U13") (pin "17") (pinfunction "PC7_(HS)_/SPI_MISO_[TIM1_CH2]_17") (pintype "unspecified"))
      (node (ref "U14") (pin "11") (pinfunction "SHCP_11") (pintype "unspecified"))
    )
    (net (code "7") (name "ACCESS") (class "Default")
      (node (ref "D2") (pin "1") (pinfunction "1_1") (pintype "unspecified"))
      (node (ref "J1") (pin "1") (pinfunction "1_1") (pintype "unspecified"))
      (node (ref "R1") (pin "1") (pinfunction "1_1") (pintype "input"))
      (node (ref "U13") (pin "13") (pinfunction "PC3_(HS)/TIM1_CH3_[TLI]_[TIM1_CH1N]_13") (pintype "unspecified"))
    )
    (net (code "8") (name "BUSIO1") (class "Default")
      (node (ref "D1") (pin "6") (pinfunction "6_6") (pintype "unspecified"))
      (node (ref "J1") (pin "8") (pinfunction "8_8") (pintype "unspecified"))
      (node (ref "R3") (pin "2") (pinfunction "2_2") (pintype "input"))
      (node (ref "U13") (pin "2") (pinfunction "UART1_TX/AIN5/(HS)_PD5_2") (pintype "unspecified"))
    )
    (net (code "9") (name "BUSIO2") (class "Default")
      (node (ref "D1") (pin "1") (pinfunction "1_1") (pintype "unspecified"))
      (node (ref "J1") (pin "9") (pinfunction "9_9") (pintype "unspecified"))
      (node (ref "R4") (pin "2") (pinfunction "2_2") (pintype "input"))
      (node (ref "U13") (pin "3") (pinfunction "UART1_RX/AIN6/(HS)_PD6_3") (pintype "unspecified"))
    )
    (net (code "10") (name "BUSIO3") (class "Default")
      (node (ref "D1") (pin "4") (pinfunction "4_4") (pintype "unspecified"))
      (node (ref "J1") (pin "12") (pinfunction "12_12") (pintype "unspecified"))
      (node (ref "R5") (pin "2") (pinfunction "2_2") (pintype "input"))
      (node (ref "U13") (pin "1") (pinfunction "UART1_CK/TIM2_CH1/BEEP/(HS)PD4_1") (pintype "unspecified"))
    )
    (net (code "11") (name "BUSIO4") (class "Default")
      (node (ref "D1") (pin "3") (pinfunction "3_3") (pintype "unspecified"))
      (node (ref "J1") (pin "15") (pinfunction "15_15") (pintype "unspecified"))
      (node (ref "R6") (pin "2") (pinfunction "2_2") (pintype "input"))
      (node (ref "U13") (pin "18") (pinfunction "PD1(HS)/SWIM_18") (pintype "unspecified"))
    )
    (net (code "12") (name "CC1") (class "Default")
      (node (ref "R13") (pin "2") (pinfunction "2_2") (pintype "input"))
      (node (ref "U13") (pin "20") (pinfunction "PD3_(HS)/AIN4/TIM2_CH2/ADC_ETR_20") (pintype "unspecified"))
      (node (ref "USB1") (pin "A5") (pinfunction "CC1_A5") (pintype "unspecified"))
    )
    (net (code "13") (name "CC2") (class "Default")
      (node (ref "R12") (pin "2") (pinfunction "2_2") (pintype "input"))
      (node (ref "U13") (pin "19") (pinfunction "PD2_(HS)/AIN3/[TIM2_CH3]_19") (pintype "unspecified"))
      (node (ref "USB1") (pin "B5") (pinfunction "CC2_B5") (pintype "unspecified"))
    )
    (net (code "14") (name "D+") (class "Default")
      (node (ref "D3") (pin "3") (pinfunction "3_3") (pintype "unspecified"))
      (node (ref "D3") (pin "4") (pinfunction "4_4") (pintype "unspecified"))
      (node (ref "U1") (pin "10") (pinfunction "DP_10") (pintype "input"))
      (node (ref "USB1") (pin "A6") (pinfunction "DP1_A6") (pintype "unspecified"))
      (node (ref "USB1") (pin "B6") (pinfunction "DP2_B6") (pintype "unspecified"))
    )
    (net (code "15") (name "D+1") (class "Default")
      (node (ref "D4") (pin "3") (pinfunction "3_3") (pintype "unspecified"))
      (node (ref "D4") (pin "4") (pinfunction "4_4") (pintype "unspecified"))
      (node (ref "U6") (pin "2") (pinfunction "HSD1+_2") (pintype "unspecified"))
      (node (ref "USB2") (pin "3") (pinfunction "D+_3") (pintype "input"))
    )
    (net (code "16") (name "D+2") (class "Default")
      (node (ref "D5") (pin "3") (pinfunction "3_3") (pintype "unspecified"))
      (node (ref "D5") (pin "4") (pinfunction "4_4") (pintype "unspecified"))
      (node (ref "U8") (pin "2") (pinfunction "HSD1+_2") (pintype "unspecified"))
      (node (ref "USB3") (pin "3") (pinfunction "D+_3") (pintype "input"))
    )
    (net (code "17") (name "D+3") (class "Default")
      (node (ref "D6") (pin "3") (pinfunction "3_3") (pintype "unspecified"))
      (node (ref "D6") (pin "4") (pinfunction "4_4") (pintype "unspecified"))
      (node (ref "U10") (pin "2") (pinfunction "HSD1+_2") (pintype "unspecified"))
      (node (ref "USB4") (pin "3") (pinfunction "D+_3") (pintype "input"))
    )
    (net (code "18") (name "D+4") (class "Default")
      (node (ref "D7") (pin "3") (pinfunction "3_3") (pintype "unspecified"))
      (node (ref "D7") (pin "4") (pinfunction "4_4") (pintype "unspecified"))
      (node (ref "U12") (pin "2") (pinfunction "HSD1+_2") (pintype "unspecified"))
      (node (ref "USB5") (pin "3") (pinfunction "D+_3") (pintype "input"))
    )
    (net (code "19") (name "D+HUB1") (class "Default")
      (node (ref "U1") (pin "8") (pinfunction "DP1_8") (pintype "input"))
      (node (ref "U6") (pin "4") (pinfunction "D+_4") (pintype "unspecified"))
    )
    (net (code "20") (name "D+HUB2") (class "Default")
      (node (ref "U1") (pin "6") (pinfunction "DP2_6") (pintype "input"))
      (node (ref "U8") (pin "4") (pinfunction "D+_4") (pintype "unspecified"))
    )
    (net (code "21") (name "D+HUB3") (class "Default")
      (node (ref "U1") (pin "4") (pinfunction "DP3_4") (pintype "input"))
      (node (ref "U10") (pin "4") (pinfunction "D+_4") (pintype "unspecified"))
    )
    (net (code "22") (name "D+HUB4") (class "Default")
      (node (ref "U1") (pin "2") (pinfunction "DP4_2") (pintype "input"))
      (node (ref "U12") (pin "4") (pinfunction "D+_4") (pintype "unspecified"))
    )
    (net (code "23") (name "D-") (class "Default")
      (node (ref "D3") (pin "1") (pinfunction "1_1") (pintype "unspecified"))
      (node (ref "D3") (pin "6") (pinfunction "6_6") (pintype "unspecified"))
      (node (ref "U1") (pin "9") (pinfunction "DM_9") (pintype "input"))
      (node (ref "USB1") (pin "A7") (pinfunction "DN1_A7") (pintype "unspecified"))
      (node (ref "USB1") (pin "B7") (pinfunction "DN2_B7") (pintype "unspecified"))
    )
    (net (code "24") (name "D-1") (class "Default")
      (node (ref "D4") (pin "1") (pinfunction "1_1") (pintype "unspecified"))
      (node (ref "D4") (pin "6") (pinfunction "6_6") (pintype "unspecified"))
      (node (ref "U6") (pin "8") (pinfunction "HSD1-_8") (pintype "unspecified"))
      (node (ref "USB2") (pin "2") (pinfunction "D-_2") (pintype "input"))
    )
    (net (code "25") (name "D-2") (class "Default")
      (node (ref "D5") (pin "1") (pinfunction "1_1") (pintype "unspecified"))
      (node (ref "D5") (pin "6") (pinfunction "6_6") (pintype "unspecified"))
      (node (ref "U8") (pin "8") (pinfunction "HSD1-_8") (pintype "unspecified"))
      (node (ref "USB3") (pin "2") (pinfunction "D-_2") (pintype "input"))
    )
    (net (code "26") (name "D-3") (class "Default")
      (node (ref "D6") (pin "1") (pinfunction "1_1") (pintype "unspecified"))
      (node (ref "D6") (pin "6") (pinfunction "6_6") (pintype "unspecified"))
      (node (ref "U10") (pin "8") (pinfunction "HSD1-_8") (pintype "unspecified"))
      (node (ref "USB4") (pin "2") (pinfunction "D-_2") (pintype "input"))
    )
    (net (code "27") (name "D-4") (class "Default")
      (node (ref "D7") (pin "1") (pinfunction "1_1") (pintype "unspecified"))
      (node (ref "D7") (pin "6") (pinfunction "6_6") (pintype "unspecified"))
      (node (ref "U12") (pin "8") (pinfunction "HSD1-_8") (pintype "unspecified"))
      (node (ref "USB5") (pin "2") (pinfunction "D-_2") (pintype "input"))
    )
    (net (code "28") (name "D-HUB1") (class "Default")
      (node (ref "U1") (pin "7") (pinfunction "DM1_7") (pintype "input"))
      (node (ref "U6") (pin "6") (pinfunction "D-_6") (pintype "unspecified"))
    )
    (net (code "29") (name "D-HUB2") (class "Default")
      (node (ref "U1") (pin "5") (pinfunction "DM2_5") (pintype "input"))
      (node (ref "U8") (pin "6") (pinfunction "D-_6") (pintype "unspecified"))
    )
    (net (code "30") (name "D-HUB3") (class "Default")
      (node (ref "U1") (pin "3") (pinfunction "DM3_3") (pintype "input"))
      (node (ref "U10") (pin "6") (pinfunction "D-_6") (pintype "unspecified"))
    )
    (net (code "31") (name "D-HUB4") (class "Default")
      (node (ref "U1") (pin "1") (pinfunction "DM4_1") (pintype "input"))
      (node (ref "U12") (pin "6") (pinfunction "D-_6") (pintype "unspecified"))
    )
    (net (code "32") (name "DATA-1") (class "Default")
      (node (ref "R22") (pin "2") (pinfunction "2_2") (pintype "input"))
      (node (ref "U14") (pin "1") (pinfunction "Q1_1") (pintype "unspecified"))
      (node (ref "U6") (pin "9") (pinfunction "OE#_9") (pintype "unspecified"))
    )
    (net (code "33") (name "DATA-2") (class "Default")
      (node (ref "R23") (pin "2") (pinfunction "2_2") (pintype "input"))
      (node (ref "U14") (pin "3") (pinfunction "Q3_3") (pintype "unspecified"))
      (node (ref "U8") (pin "9") (pinfunction "OE#_9") (pintype "unspecified"))
    )
    (net (code "34") (name "DATA-3") (class "Default")
      (node (ref "R24") (pin "2") (pinfunction "2_2") (pintype "input"))
      (node (ref "U10") (pin "9") (pinfunction "OE#_9") (pintype "unspecified"))
      (node (ref "U14") (pin "5") (pinfunction "Q5_5") (pintype "unspecified"))
    )
    (net (code "35") (name "DATA-4") (class "Default")
      (node (ref "R25") (pin "2") (pinfunction "2_2") (pintype "input"))
      (node (ref "U12") (pin "9") (pinfunction "OE#_9") (pintype "unspecified"))
      (node (ref "U14") (pin "7") (pinfunction "Q7_7") (pintype "unspecified"))
    )
    (net (code "36") (name "GND") (class "Default")
      (node (ref "C1") (pin "1") (pinfunction "1_1") (pintype "input"))
      (node (ref "C10") (pin "2") (pinfunction "2_2") (pintype "unspecified"))
      (node (ref "C11") (pin "2") (pinfunction "2_2") (pintype "unspecified"))
      (node (ref "C12") (pin "1") (pinfunction "1_1") (pintype "unspecified"))
      (node (ref "C13") (pin "1") (pinfunction "1_1") (pintype "input"))
      (node (ref "C14") (pin "2") (pinfunction "2_2") (pintype "unspecified"))
      (node (ref "C15") (pin "2") (pinfunction "2_2") (pintype "unspecified"))
      (node (ref "C16") (pin "2") (pinfunction "2_2") (pintype "unspecified"))
      (node (ref "C17") (pin "1") (pinfunction "1_1") (pintype "unspecified"))
      (node (ref "C18") (pin "1") (pinfunction "1_1") (pintype "input"))
      (node (ref "C19") (pin "2") (pinfunction "2_2") (pintype "unspecified"))
      (node (ref "C2") (pin "1") (pinfunction "1_1") (pintype "input"))
      (node (ref "C20") (pin "2") (pinfunction "2_2") (pintype "unspecified"))
      (node (ref "C21") (pin "2") (pinfunction "2_2") (pintype "unspecified"))
      (node (ref "C22") (pin "1") (pinfunction "1_1") (pintype "unspecified"))
      (node (ref "C23") (pin "1") (pinfunction "1_1") (pintype "input"))
      (node (ref "C24") (pin "2") (pinfunction "2_2") (pintype "unspecified"))
      (node (ref "C25") (pin "2") (pinfunction "2_2") (pintype "unspecified"))
      (node (ref "C26") (pin "2") (pinfunction "2_2") (pintype "unspecified"))
      (node (ref "C27") (pin "1") (pinfunction "1_1") (pintype "unspecified"))
      (node (ref "C28") (pin "1") (pinfunction "1_1") (pintype "input"))
      (node (ref "C29") (pin "2") (pinfunction "2_2") (pintype "input"))
      (node (ref "C3") (pin "1") (pinfunction "1_1") (pintype "input"))
      (node (ref "C30") (pin "1") (pinfunction "1_1") (pintype "unspecified"))
      (node (ref "C31") (pin "1") (pinfunction "1_1") (pintype "unspecified"))
      (node (ref "C32") (pin "1") (pinfunction "1_1") (pintype "unspecified"))
      (node (ref "C33") (pin "1") (pinfunction "1_1") (pintype "unspecified"))
      (node (ref "C34") (pin "1") (pinfunction "1_1") (pintype "unspecified"))
      (node (ref "C4") (pin "1") (pinfunction "1_1") (pintype "input"))
      (node (ref "C5") (pin "1") (pinfunction "1_1") (pintype "unspecified"))
      (node (ref "C6") (pin "1") (pinfunction "1_1") (pintype "input"))
      (node (ref "C7") (pin "1") (pinfunction "1_1") (pintype "input"))
      (node (ref "C8") (pin "2") (pinfunction "2_2") (pintype "input"))
      (node (ref "C9") (pin "2") (pinfunction "2_2") (pintype "unspecified"))
      (node (ref "D1") (pin "2") (pinfunction "2_2") (pintype "unspecified"))
      (node (ref "D2") (pin "2") (pinfunction "2_2") (pintype "unspecified"))
      (node (ref "D3") (pin "2") (pinfunction "2_2") (pintype "unspecified"))
      (node (ref "D4") (pin "2") (pinfunction "2_2") (pintype "unspecified"))
      (node (ref "D5") (pin "2") (pinfunction "2_2") (pintype "unspecified"))
      (node (ref "D6") (pin "2") (pinfunction "2_2") (pintype "unspecified"))
      (node (ref "D7") (pin "2") (pinfunction "2_2") (pintype "unspecified"))
      (node (ref "J1") (pin "10") (pinfunction "10_10") (pintype "unspecified"))
      (node (ref "J1") (pin "11") (pinfunction "11_11") (pintype "unspecified"))
      (node (ref "J1") (pin "14") (pinfunction "14_14") (pintype "unspecified"))
      (node (ref "J1") (pin "3") (pinfunction "3_3") (pintype "unspecified"))
      (node (ref "R1") (pin "2") (pinfunction "2_2") (pintype "input"))
      (node (ref "R12") (pin "1") (pinfunction "1_1") (pintype "input"))
      (node (ref "R13") (pin "1") (pinfunction "1_1") (pintype "input"))
      (node (ref "R14") (pin "1") (pinfunction "1_1") (pintype "input"))
      (node (ref "R15") (pin "1") (pinfunction "1_1") (pintype "input"))
      (node (ref "R16") (pin "1") (pinfunction "1_1") (pintype "input"))
      (node (ref "R17") (pin "1") (pinfunction "1_1") (pintype "input"))
      (node (ref "R2") (pin "1") (pinfunction "1_1") (pintype "input"))
      (node (ref "R26") (pin "1") (pinfunction "1_1") (pintype "input"))
      (node (ref "R27") (pin "1") (pinfunction "1_1") (pintype "input"))
      (node (ref "R28") (pin "1") (pinfunction "1_1") (pintype "input"))
      (node (ref "R29") (pin "1") (pinfunction "1_1") (pintype "input"))
      (node (ref "R3") (pin "1") (pinfunction "1_1") (pintype "input"))
      (node (ref "R4") (pin "1") (pinfunction "1_1") (pintype "input"))
      (node (ref "R5") (pin "1") (pinfunction "1_1") (pintype "input"))
      (node (ref "R6") (pin "1") (pinfunction "1_1") (pintype "input"))
      (node (ref "R7") (pin "1") (pinfunction "1_1") (pintype "input"))
      (node (ref "SW1") (pin "2") (pinfunction "2_2") (pintype "unspecified"))
      (node (ref "U1") (pin "12") (pinfunction "GND_12") (pintype "input"))
      (node (ref "U10") (pin "1") (pinfunction "Sel_1") (pintype "unspecified"))
      (node (ref "U10") (pin "5") (pinfunction "GND_5") (pintype "unspecified"))
      (node (ref "U11") (pin "2") (pinfunction "GND_2") (pintype "unspecified"))
      (node (ref "U12") (pin "1") (pinfunction "Sel_1") (pintype "unspecified"))
      (node (ref "U12") (pin "5") (pinfunction "GND_5") (pintype "unspecified"))
      (node (ref "U13") (pin "7") (pinfunction "VSS_7") (pintype "unspecified"))
      (node (ref "U14") (pin "13") (pinfunction "OE#_13") (pintype "unspecified"))
      (node (ref "U14") (pin "8") (pinfunction "GND_8") (pintype "unspecified"))
      (node (ref "U15") (pin "7") (pinfunction "GND_7") (pintype "unspecified"))
      (node (ref "U2") (pin "5") (pinfunction "GND_5") (pintype "unspecified"))
      (node (ref "U3") (pin "2") (pinfunction "GND_2") (pintype "unspecified"))
      (node (ref "U4") (pin "2") (pinfunction "GND_2") (pintype "unspecified"))
      (node (ref "U4") (pin "4") (pinfunction "EN#_4") (pintype "unspecified"))
      (node (ref "U5") (pin "2") (pinfunction "GND_2") (pintype "unspecified"))
      (node (ref "U6") (pin "1") (pinfunction "Sel_1") (pintype "unspecified"))
      (node (ref "U6") (pin "5") (pinfunction "GND_5") (pintype "unspecified"))
      (node (ref "U7") (pin "2") (pinfunction "GND_2") (pintype "unspecified"))
      (node (ref "U8") (pin "1") (pinfunction "Sel_1") (pintype "unspecified"))
      (node (ref "U8") (pin "5") (pinfunction "GND_5") (pintype "unspecified"))
      (node (ref "U9") (pin "2") (pinfunction "GND_2") (pintype "unspecified"))
      (node (ref "USB1") (pin "A1B12") (pinfunction "GND_A1B12") (pintype "unspecified"))
      (node (ref "USB1") (pin "B1A12") (pinfunction "GND_B1A12") (pintype "unspecified"))
      (node (ref "USB2") (pin "4") (pinfunction "GND_4") (pintype "input"))
      (node (ref "USB2") (pin "SH1") (pinfunction "SH1_SH1") (pintype "unspecified"))
      (node (ref "USB2") (pin "SH2") (pinfunction "SH2_SH2") (pintype "unspecified"))
      (node (ref "USB3") (pin "4") (pinfunction "GND_4") (pintype "input"))
      (node (ref "USB3") (pin "SH1") (pinfunction "SH1_SH1") (pintype "unspecified"))
      (node (ref "USB3") (pin "SH2") (pinfunction "SH2_SH2") (pintype "unspecified"))
      (node (ref "USB4") (pin "4") (pinfunction "GND_4") (pintype "input"))
      (node (ref "USB4") (pin "SH1") (pinfunction "SH1_SH1") (pintype "unspecified"))
      (node (ref "USB4") (pin "SH2") (pinfunction "SH2_SH2") (pintype "unspecified"))
      (node (ref "USB5") (pin "4") (pinfunction "GND_4") (pintype "input"))
      (node (ref "USB5") (pin "SH1") (pinfunction "SH1_SH1") (pintype "unspecified"))
      (node (ref "USB5") (pin "SH2") (pinfunction "SH2_SH2") (pintype "unspecified"))
      (node (ref "X1") (pin "2") (pinfunction "GND_2") (pintype "input"))
      (node (ref "X1") (pin "4") (pinfunction "GND_4") (pintype "input"))
    )
    (net (code "37") (name "INTERRUPT") (class "Default")
      (node (ref "D2") (pin "6") (pinfunction "6_6") (pintype "unspecified"))
      (node (ref "J1") (pin "7") (pinfunction "7_7") (pintype "unspecified"))
      (node (ref "R2") (pin "2") (pinfunction "2_2") (pintype "input"))
      (node (ref "U11") (pin "3") (pinfunction "FLAG#_3") (pintype "unspecified"))
      (node (ref "U13") (pin "14") (pinfunction "PC4_(HS)_/TIM1_CH4/CLK_CCO/AIN2/[TIM1_CH2N]_14") (pintype "unspecified"))
      (node (ref "U4") (pin "3") (pinfunction "FLAG#_3") (pintype "unspecified"))
      (node (ref "U5") (pin "3") (pinfunction "FLAG#_3") (pintype "unspecified"))
      (node (ref "U7") (pin "3") (pinfunction "FLAG#_3") (pintype "unspecified"))
      (node (ref "U9") (pin "3") (pinfunction "FLAG#_3") (pintype "unspecified"))
    )
    (net (code "38") (name "MODE1") (class "Default")
      (node (ref "R32") (pin "2") (pinfunction "2_2") (pintype "input"))
      (node (ref "SW1") (pin "1") (pinfunction "1_1") (pintype "unspecified"))
      (node (ref "U13") (pin "5") (pinfunction "OSCIN/PA1_5") (pintype "unspecified"))
    )
    (net (code "39") (name "MODE2") (class "Default")
      (node (ref "R30") (pin "2") (pinfunction "2_2") (pintype "input"))
      (node (ref "SW1") (pin "3") (pinfunction "3_3") (pintype "unspecified"))
      (node (ref "U13") (pin "10") (pinfunction "[SPI_NSS]_TIM2_CH3/(HS)_PA3_10") (pintype "unspecified"))
    )
    (net (code "40") (name "MODE3") (class "Default")
      (node (ref "R31") (pin "2") (pinfunction "2_2") (pintype "input"))
      (node (ref "SW1") (pin "4") (pinfunction "4_4") (pintype "unspecified"))
      (node (ref "U13") (pin "6") (pinfunction "OSCOUT/PA2_6") (pintype "unspecified"))
    )
    (net (code "41") (name "Net-(LED1--)") (class "Default")
      (node (ref "LED1") (pin "2") (pinfunction "-_2") (pintype "unspecified"))
      (node (ref "R29") (pin "2") (pinfunction "2_2") (pintype "input"))
    )
    (net (code "42") (name "Net-(LED2--)") (class "Default")
      (node (ref "LED2") (pin "2") (pinfunction "-_2") (pintype "unspecified"))
      (node (ref "R28") (pin "2") (pinfunction "2_2") (pintype "input"))
    )
    (net (code "43") (name "Net-(LED3--)") (class "Default")
      (node (ref "LED3") (pin "2") (pinfunction "-_2") (pintype "unspecified"))
      (node (ref "R27") (pin "2") (pinfunction "2_2") (pintype "input"))
    )
    (net (code "44") (name "Net-(LED4--)") (class "Default")
      (node (ref "LED4") (pin "2") (pinfunction "-_2") (pintype "unspecified"))
      (node (ref "R26") (pin "2") (pinfunction "2_2") (pintype "input"))
    )
    (net (code "45") (name "Net-(U1-VDD18)") (class "Default")
      (node (ref "C2") (pin "2") (pinfunction "2_2") (pintype "input"))
      (node (ref "U1") (pin "14") (pinfunction "VDD18_14") (pintype "input"))
    )
    (net (code "46") (name "Net-(U1-VDD33)") (class "Default")
      (node (ref "C1") (pin "2") (pinfunction "2_2") (pintype "input"))
      (node (ref "U1") (pin "13") (pinfunction "VDD33_13") (pintype "input"))
    )
    (net (code "47") (name "Net-(U1-XIN)") (class "Default")
      (node (ref "U1") (pin "16") (pinfunction "XIN_16") (pintype "input"))
      (node (ref "X1") (pin "3") (pinfunction "OSC2_3") (pintype "input"))
    )
    (net (code "48") (name "Net-(U1-XOUT)") (class "Default")
      (node (ref "U1") (pin "15") (pinfunction "XOUT_15") (pintype "input"))
      (node (ref "X1") (pin "1") (pinfunction "OSC1_1") (pintype "input"))
    )
    (net (code "49") (name "Net-(U4-ISET)") (class "Default")
      (node (ref "R10") (pin "2") (pinfunction "2_2") (pintype "input"))
      (node (ref "R11") (pin "2") (pinfunction "2_2") (pintype "input"))
      (node (ref "R7") (pin "2") (pinfunction "2_2") (pintype "input"))
      (node (ref "R8") (pin "2") (pinfunction "2_2") (pintype "input"))
      (node (ref "R9") (pin "2") (pinfunction "2_2") (pintype "input"))
      (node (ref "U4") (pin "5") (pinfunction "ISET_5") (pintype "unspecified"))
    )
    (net (code "50") (name "Net-(U5-ISET)") (class "Default")
      (node (ref "R14") (pin "2") (pinfunction "2_2") (pintype "input"))
      (node (ref "U5") (pin "5") (pinfunction "ISET_5") (pintype "unspecified"))
    )
    (net (code "51") (name "Net-(U7-ISET)") (class "Default")
      (node (ref "R15") (pin "2") (pinfunction "2_2") (pintype "input"))
      (node (ref "U7") (pin "5") (pinfunction "ISET_5") (pintype "unspecified"))
    )
    (net (code "52") (name "Net-(U9-ISET)") (class "Default")
      (node (ref "R16") (pin "2") (pinfunction "2_2") (pintype "input"))
      (node (ref "U9") (pin "5") (pinfunction "ISET_5") (pintype "unspecified"))
    )
    (net (code "53") (name "Net-(U11-ISET)") (class "Default")
      (node (ref "R17") (pin "2") (pinfunction "2_2") (pintype "input"))
      (node (ref "U11") (pin "5") (pinfunction "ISET_5") (pintype "unspecified"))
    )
    (net (code "54") (name "Net-(U13-VCAP)") (class "Default")
      (node (ref "C32") (pin "2") (pinfunction "2_2") (pintype "unspecified"))
      (node (ref "U13") (pin "8") (pinfunction "VCAP_8") (pintype "unspecified"))
    )
    (net (code "55") (name "ONEWIRE") (class "Default")
      (node (ref "D2") (pin "4") (pinfunction "4_4") (pintype "unspecified"))
      (node (ref "J1") (pin "2") (pinfunction "2_2") (pintype "unspecified"))
      (node (ref "U2") (pin "4") (pinfunction "DQ_4") (pintype "unspecified"))
    )
    (net (code "56") (name "POWER-1") (class "Default")
      (node (ref "R21") (pin "2") (pinfunction "2_2") (pintype "input"))
      (node (ref "U14") (pin "15") (pinfunction "Q0_15") (pintype "unspecified"))
      (node (ref "U5") (pin "4") (pinfunction "EN#_4") (pintype "unspecified"))
    )
    (net (code "57") (name "POWER-2") (class "Default")
      (node (ref "R20") (pin "2") (pinfunction "2_2") (pintype "input"))
      (node (ref "U14") (pin "2") (pinfunction "Q2_2") (pintype "unspecified"))
      (node (ref "U7") (pin "4") (pinfunction "EN#_4") (pintype "unspecified"))
    )
    (net (code "58") (name "POWER-3") (class "Default")
      (node (ref "R19") (pin "2") (pinfunction "2_2") (pintype "input"))
      (node (ref "U14") (pin "4") (pinfunction "Q4_4") (pintype "unspecified"))
      (node (ref "U9") (pin "4") (pinfunction "EN#_4") (pintype "unspecified"))
    )
    (net (code "59") (name "POWER-4") (class "Default")
      (node (ref "R18") (pin "2") (pinfunction "2_2") (pintype "input"))
      (node (ref "U11") (pin "4") (pinfunction "EN#_4") (pintype "unspecified"))
      (node (ref "U14") (pin "6") (pinfunction "Q6_6") (pintype "unspecified"))
    )
    (net (code "60") (name "POWER1") (class "Default")
      (node (ref "LED1") (pin "1") (pinfunction "+_1") (pintype "unspecified"))
      (node (ref "U15") (pin "2") (pinfunction "1Y_2") (pintype "unspecified"))
    )
    (net (code "61") (name "POWER2") (class "Default")
      (node (ref "LED2") (pin "1") (pinfunction "+_1") (pintype "unspecified"))
      (node (ref "U15") (pin "4") (pinfunction "2Y_4") (pintype "unspecified"))
    )
    (net (code "62") (name "POWER3") (class "Default")
      (node (ref "LED3") (pin "1") (pinfunction "+_1") (pintype "unspecified"))
      (node (ref "U15") (pin "6") (pinfunction "3Y_6") (pintype "unspecified"))
    )
    (net (code "63") (name "POWER4") (class "Default")
      (node (ref "LED4") (pin "1") (pinfunction "+_1") (pintype "unspecified"))
      (node (ref "U15") (pin "8") (pinfunction "4Y_8") (pintype "unspecified"))
    )
    (net (code "64") (name "VDS1") (class "Default")
      (node (ref "C10") (pin "1") (pinfunction "1_1") (pintype "unspecified"))
      (node (ref "C11") (pin "1") (pinfunction "1_1") (pintype "unspecified"))
      (node (ref "C9") (pin "1") (pinfunction "1_1") (pintype "unspecified"))
      (node (ref "D4") (pin "5") (pinfunction "5_5") (pintype "unspecified"))
      (node (ref "LED1") (pin "3") (pinfunction "+_3") (pintype "unspecified"))
      (node (ref "U15") (pin "1") (pinfunction "1A_1") (pintype "unspecified"))
      (node (ref "U5") (pin "1") (pinfunction "VOUT_1") (pintype "unspecified"))
      (node (ref "USB2") (pin "1") (pinfunction "VCC_1") (pintype "input"))
    )
    (net (code "65") (name "VDS2") (class "Default")
      (node (ref "C14") (pin "1") (pinfunction "1_1") (pintype "unspecified"))
      (node (ref "C15") (pin "1") (pinfunction "1_1") (pintype "unspecified"))
      (node (ref "C16") (pin "1") (pinfunction "1_1") (pintype "unspecified"))
      (node (ref "D5") (pin "5") (pinfunction "5_5") (pintype "unspecified"))
      (node (ref "LED2") (pin "3") (pinfunction "+_3") (pintype "unspecified"))
      (node (ref "U15") (pin "3") (pinfunction "2A_3") (pintype "unspecified"))
      (node (ref "U7") (pin "1") (pinfunction "VOUT_1") (pintype "unspecified"))
      (node (ref "USB3") (pin "1") (pinfunction "VCC_1") (pintype "input"))
    )
    (net (code "66") (name "VDS3") (class "Default")
      (node (ref "C19") (pin "1") (pinfunction "1_1") (pintype "unspecified"))
      (node (ref "C20") (pin "1") (pinfunction "1_1") (pintype "unspecified"))
      (node (ref "C21") (pin "1") (pinfunction "1_1") (pintype "unspecified"))
      (node (ref "D6") (pin "5") (pinfunction "5_5") (pintype "unspecified"))
      (node (ref "LED3") (pin "3") (pinfunction "+_3") (pintype "unspecified"))
      (node (ref "U15") (pin "5") (pinfunction "3A_5") (pintype "unspecified"))
      (node (ref "U9") (pin "1") (pinfunction "VOUT_1") (pintype "unspecified"))
      (node (ref "USB4") (pin "1") (pinfunction "VCC_1") (pintype "input"))
    )
    (net (code "67") (name "VDS4") (class "Default")
      (node (ref "C24") (pin "1") (pinfunction "1_1") (pintype "unspecified"))
      (node (ref "C25") (pin "1") (pinfunction "1_1") (pintype "unspecified"))
      (node (ref "C26") (pin "1") (pinfunction "1_1") (pintype "unspecified"))
      (node (ref "D7") (pin "5") (pinfunction "5_5") (pintype "unspecified"))
      (node (ref "LED4") (pin "3") (pinfunction "+_3") (pintype "unspecified"))
      (node (ref "U11") (pin "1") (pinfunction "VOUT_1") (pintype "unspecified"))
      (node (ref "U15") (pin "9") (pinfunction "4A_9") (pintype "unspecified"))
      (node (ref "USB5") (pin "1") (pinfunction "VCC_1") (pintype "input"))
    )
    (net (code "68") (name "VIN") (class "Default")
      (node (ref "C13") (pin "2") (pinfunction "2_2") (pintype "input"))
      (node (ref "C18") (pin "2") (pinfunction "2_2") (pintype "input"))
      (node (ref "C23") (pin "2") (pinfunction "2_2") (pintype "input"))
      (node (ref "C28") (pin "2") (pinfunction "2_2") (pintype "input"))
      (node (ref "C4") (pin "2") (pinfunction "2_2") (pintype "input"))
      (node (ref "C5") (pin "2") (pinfunction "2_2") (pintype "unspecified"))
      (node (ref "C8") (pin "1") (pinfunction "1_1") (pintype "input"))
      (node (ref "R18") (pin "1") (pinfunction "1_1") (pintype "input"))
      (node (ref "R19") (pin "1") (pinfunction "1_1") (pintype "input"))
      (node (ref "R20") (pin "1") (pinfunction "1_1") (pintype "input"))
      (node (ref "R21") (pin "1") (pinfunction "1_1") (pintype "input"))
      (node (ref "U1") (pin "11") (pinfunction "VDD5_11") (pintype "input"))
      (node (ref "U11") (pin "6") (pinfunction "VIN_6") (pintype "unspecified"))
      (node (ref "U3") (pin "1") (pinfunction "VIN_1") (pintype "unspecified"))
      (node (ref "U3") (pin "3") (pinfunction "ON_3") (pintype "unspecified"))
      (node (ref "U4") (pin "1") (pinfunction "VOUT_1") (pintype "unspecified"))
      (node (ref "U5") (pin "6") (pinfunction "VIN_6") (pintype "unspecified"))
      (node (ref "U7") (pin "6") (pinfunction "VIN_6") (pintype "unspecified"))
      (node (ref "U9") (pin "6") (pinfunction "VIN_6") (pintype "unspecified"))
    )
    (net (code "69") (name "VUSB") (class "Default")
      (node (ref "C7") (pin "2") (pinfunction "2_2") (pintype "input"))
      (node (ref "D3") (pin "5") (pinfunction "5_5") (pintype "unspecified"))
      (node (ref "U4") (pin "6") (pinfunction "VIN_6") (pintype "unspecified"))
      (node (ref "USB1") (pin "A4B9") (pinfunction "VBUS_A4B9") (pintype "unspecified"))
      (node (ref "USB1") (pin "B4A9") (pinfunction "VBUS_B4A9") (pintype "unspecified"))
    )
    (net (code "70") (name "unconnected-(D2-Pad3)") (class "Default")
      (node (ref "D2") (pin "3") (pinfunction "3_3") (pintype "unspecified+no_connect"))
    )
    (net (code "71") (name "unconnected-(J1-Pad4)") (class "Default")
      (node (ref "J1") (pin "4") (pinfunction "4_4") (pintype "unspecified+no_connect"))
    )
    (net (code "72") (name "unconnected-(J1-Pad5)") (class "Default")
      (node (ref "J1") (pin "5") (pinfunction "5_5") (pintype "unspecified+no_connect"))
    )
    (net (code "73") (name "unconnected-(J1-Pad16)") (class "Default")
      (node (ref "J1") (pin "16") (pinfunction "16_16") (pintype "unspecified+no_connect"))
    )
    (net (code "74") (name "unconnected-(J1-Pad17)") (class "Default")
      (node (ref "J1") (pin "17") (pinfunction "17_17") (pintype "unspecified+no_connect"))
    )
    (net (code "75") (name "unconnected-(SW1-Pad5)") (class "Default")
      (node (ref "SW1") (pin "5") (pinfunction "5_5") (pintype "unspecified+no_connect"))
    )
    (net (code "76") (name "unconnected-(SW1-Pad6)") (class "Default")
      (node (ref "SW1") (pin "6") (pinfunction "6_6") (pintype "unspecified+no_connect"))
    )
    (net (code "77") (name "unconnected-(SW1-Pad7)") (class "Default")
      (node (ref "SW1") (pin "7") (pinfunction "7_7") (pintype "unspecified+no_connect"))
    )
    (net (code "78") (name "unconnected-(SW1-Pad8)") (class "Default")
      (node (ref "SW1") (pin "8") (pinfunction "8_8") (pintype "unspecified+no_connect"))
    )
    (net (code "79") (name "unconnected-(U2-NC-Pad1)") (class "Default")
      (node (ref "U2") (pin "1") (pinfunction "NC_1") (pintype "unspecified+no_connect"))
    )
    (net (code "80") (name "unconnected-(U2-NC-Pad2)") (class "Default")
      (node (ref "U2") (pin "2") (pinfunction "NC_2") (pintype "unspecified+no_connect"))
    )
    (net (code "81") (name "unconnected-(U2-NC-Pad6)") (class "Default")
      (node (ref "U2") (pin "6") (pinfunction "NC_6") (pintype "unspecified+no_connect"))
    )
    (net (code "82") (name "unconnected-(U2-NC-Pad7)") (class "Default")
      (node (ref "U2") (pin "7") (pinfunction "NC_7") (pintype "unspecified+no_connect"))
    )
    (net (code "83") (name "unconnected-(U2-NC-Pad8)") (class "Default")
      (node (ref "U2") (pin "8") (pinfunction "NC_8") (pintype "unspecified+no_connect"))
    )
    (net (code "84") (name "unconnected-(U3-NC-Pad4)") (class "Default")
      (node (ref "U3") (pin "4") (pinfunction "NC_4") (pintype "unspecified+no_connect"))
    )
    (net (code "85") (name "unconnected-(U3-NC-Pad5)") (class "Default")
      (node (ref "U3") (pin "5") (pinfunction "NC_5") (pintype "unspecified+no_connect"))
    )
    (net (code "86") (name "unconnected-(U6-HSD2+-Pad3)") (class "Default")
      (node (ref "U6") (pin "3") (pinfunction "HSD2+_3") (pintype "unspecified+no_connect"))
    )
    (net (code "87") (name "unconnected-(U6-HSD2--Pad7)") (class "Default")
      (node (ref "U6") (pin "7") (pinfunction "HSD2-_7") (pintype "unspecified+no_connect"))
    )
    (net (code "88") (name "unconnected-(U8-HSD2+-Pad3)") (class "Default")
      (node (ref "U8") (pin "3") (pinfunction "HSD2+_3") (pintype "unspecified+no_connect"))
    )
    (net (code "89") (name "unconnected-(U8-HSD2--Pad7)") (class "Default")
      (node (ref "U8") (pin "7") (pinfunction "HSD2-_7") (pintype "unspecified+no_connect"))
    )
    (net (code "90") (name "unconnected-(U10-HSD2+-Pad3)") (class "Default")
      (node (ref "U10") (pin "3") (pinfunction "HSD2+_3") (pintype "unspecified+no_connect"))
    )
    (net (code "91") (name "unconnected-(U10-HSD2--Pad7)") (class "Default")
      (node (ref "U10") (pin "7") (pinfunction "HSD2-_7") (pintype "unspecified+no_connect"))
    )
    (net (code "92") (name "unconnected-(U12-HSD2+-Pad3)") (class "Default")
      (node (ref "U12") (pin "3") (pinfunction "HSD2+_3") (pintype "unspecified+no_connect"))
    )
    (net (code "93") (name "unconnected-(U12-HSD2--Pad7)") (class "Default")
      (node (ref "U12") (pin "7") (pinfunction "HSD2-_7") (pintype "unspecified+no_connect"))
    )
    (net (code "94") (name "unconnected-(U13-NRST-Pad4)") (class "Default")
      (node (ref "U13") (pin "4") (pinfunction "NRST_4") (pintype "unspecified+no_connect"))
    )
    (net (code "95") (name "unconnected-(U14-Q7S-Pad9)") (class "Default")
      (node (ref "U14") (pin "9") (pinfunction "Q7S_9") (pintype "unspecified+no_connect"))
    )
    (net (code "96") (name "unconnected-(U15-5Y-Pad10)") (class "Default")
      (node (ref "U15") (pin "10") (pinfunction "5Y_10") (pintype "unspecified+no_connect"))
    )
    (net (code "97") (name "unconnected-(U15-6Y-Pad12)") (class "Default")
      (node (ref "U15") (pin "12") (pinfunction "6Y_12") (pintype "unspecified+no_connect"))
    )
    (net (code "98") (name "unconnected-(USB1-SBU1-PadA8)") (class "Default")
      (node (ref "USB1") (pin "A8") (pinfunction "SBU1_A8") (pintype "unspecified+no_connect"))
    )
    (net (code "99") (name "unconnected-(USB1-SBU2-PadB8)") (class "Default")
      (node (ref "USB1") (pin "B8") (pinfunction "SBU2_B8") (pintype "unspecified+no_connect"))
    )
    (net (code "100") (name "unconnected-(USB1-SHELL-Pad1)") (class "Default")
      (node (ref "USB1") (pin "1") (pinfunction "SHELL_1") (pintype "unspecified+no_connect"))
    )
  )
)
